# SupplyBox_v4.net
KiCad netlist of a schematic drawn in Altium Designer
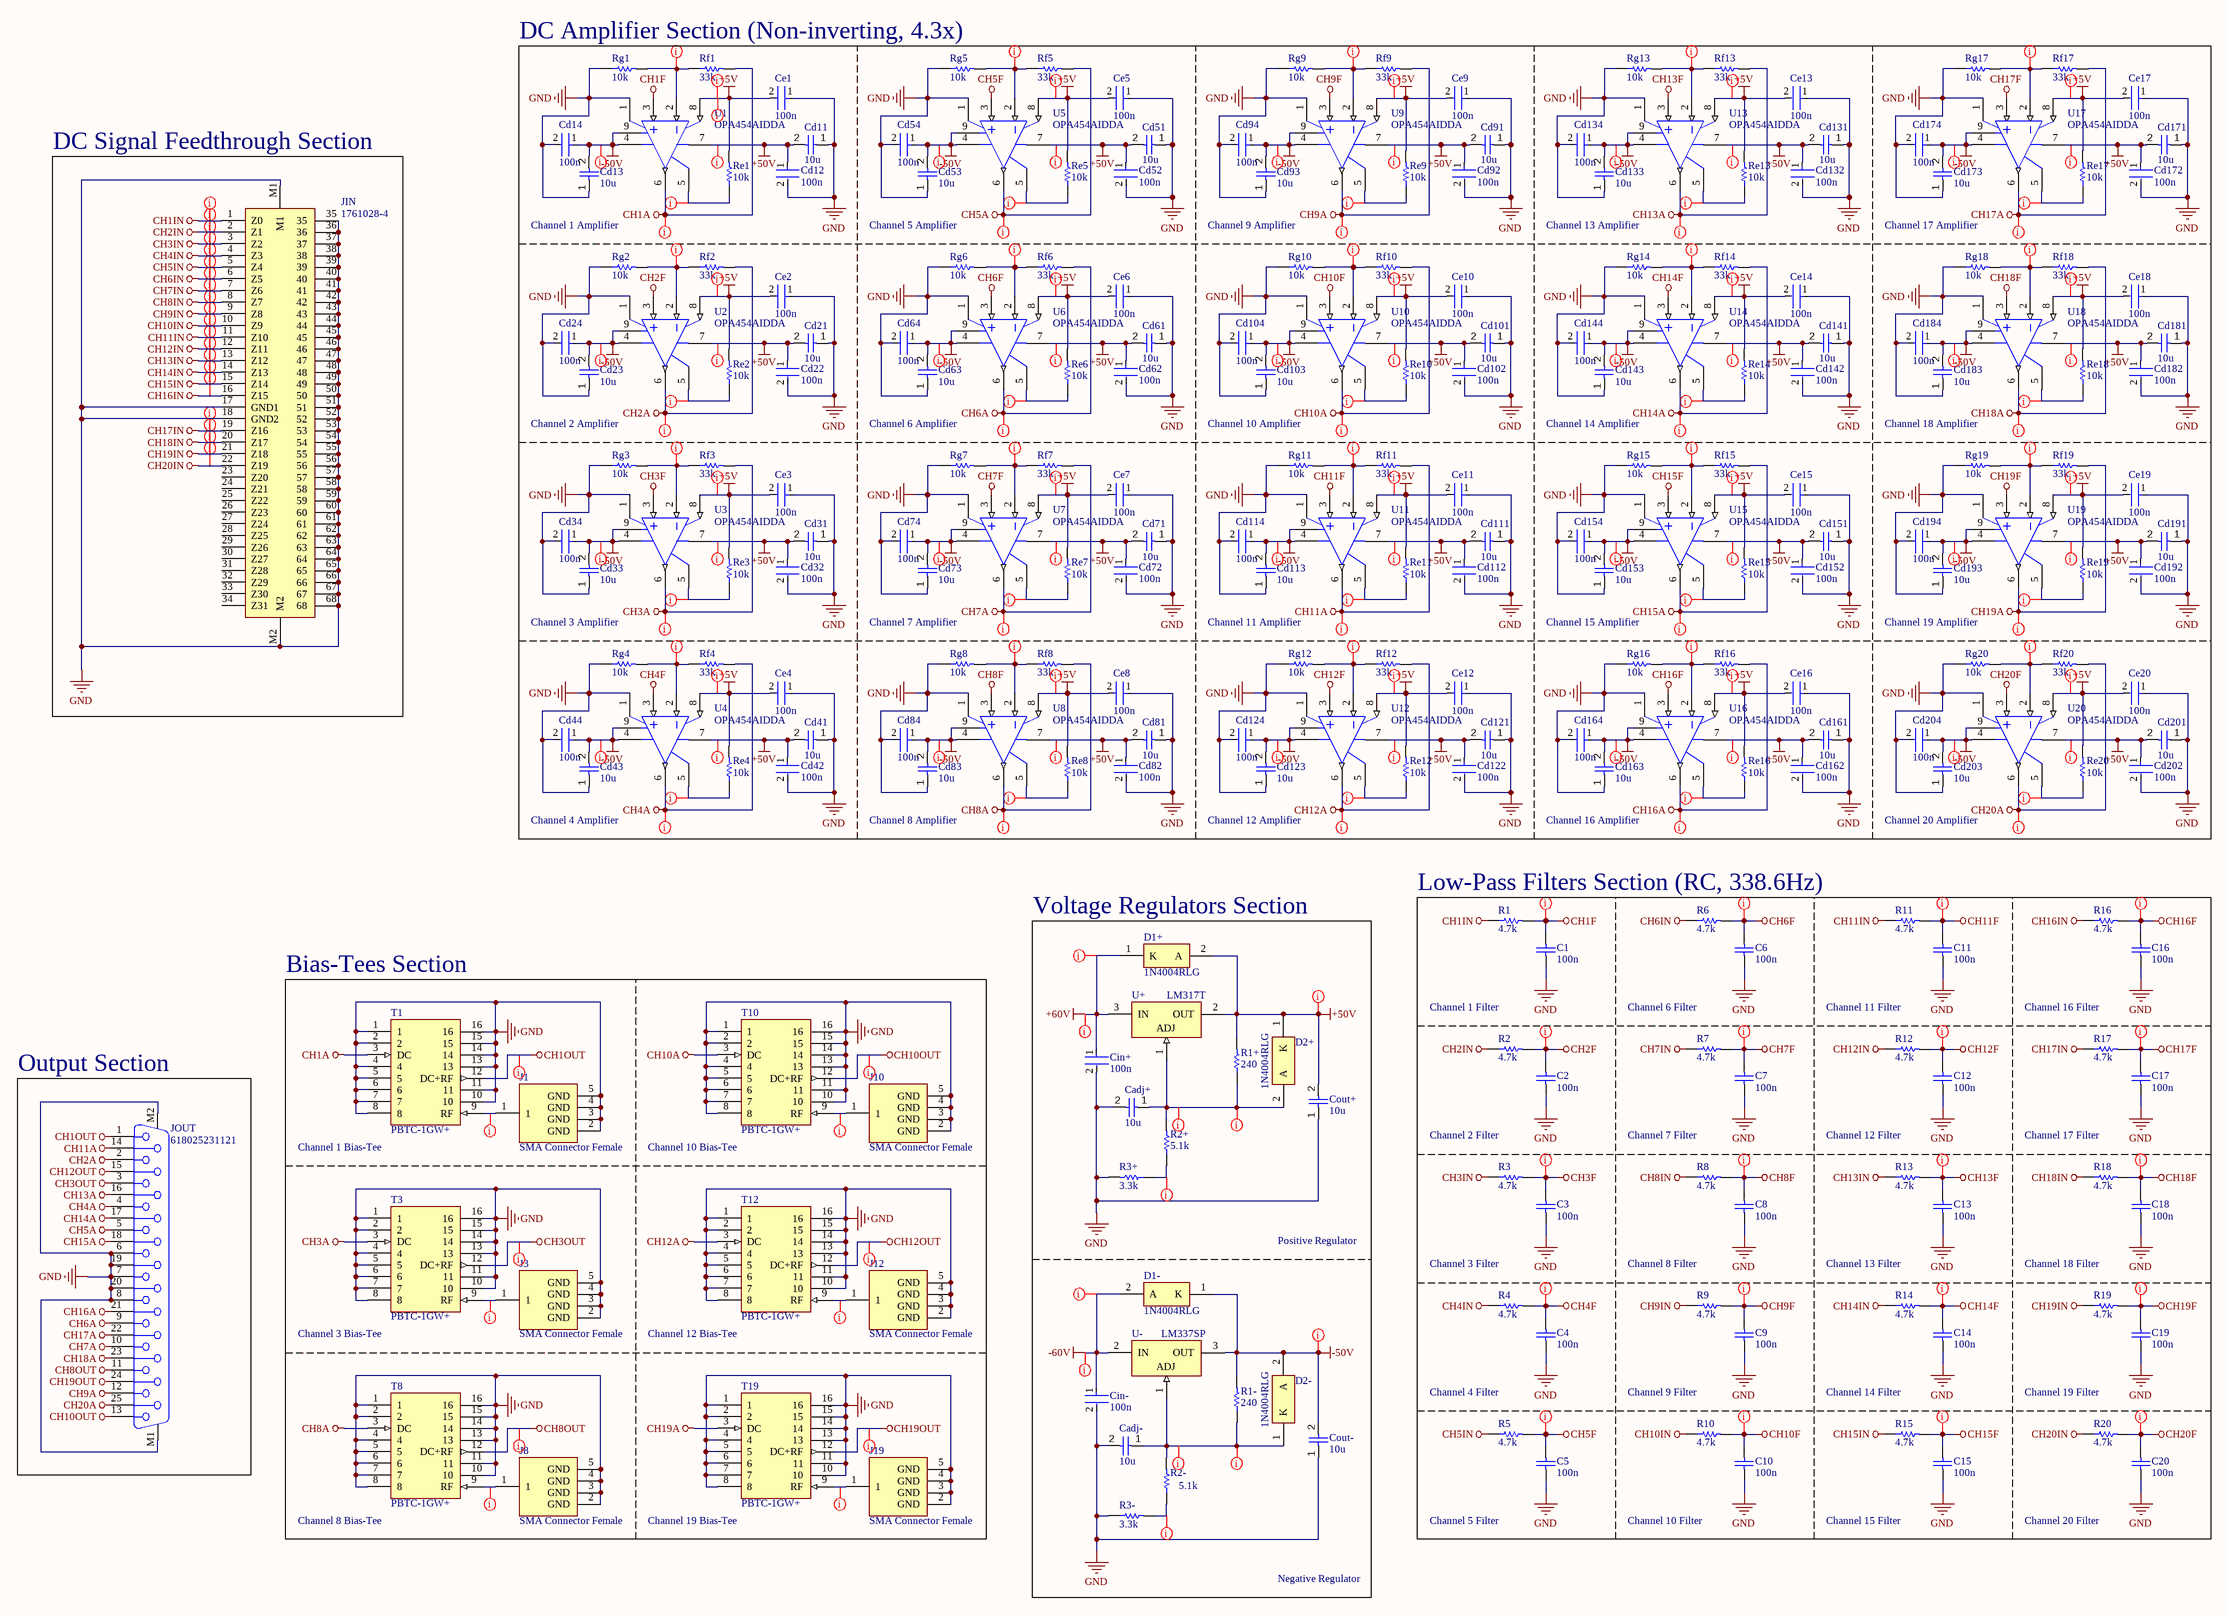
[diagram p0: SupplyBox_v4.SchDoc]

(export (version "E")
  (design (tool "Eeschema 10.0.6"))
  (components
    (comp (ref "C1")
      (value "100n")
      (footprint "CAPC2013X145X48NL20T23")
      (fields (field (name "MANUFACTURER") "Vitramon") (field (name "PART NUMBER") "VJ0805Y104KNAAT"))
      (libsource (lib "Altium Content Vault") (part "CAP"))
    )
    (comp (ref "C2")
      (value "100n")
      (footprint "CAPC2013X145X48NL20T23")
      (fields (field (name "MANUFACTURER") "Vitramon") (field (name "PART NUMBER") "VJ0805Y104KNAAT"))
      (libsource (lib "Altium Content Vault") (part "CAP"))
    )
    (comp (ref "C3")
      (value "100n")
      (footprint "CAPC2013X145X48NL20T23")
      (fields (field (name "MANUFACTURER") "Vitramon") (field (name "PART NUMBER") "VJ0805Y104KNAAT"))
      (libsource (lib "Altium Content Vault") (part "CAP"))
    )
    (comp (ref "C4")
      (value "100n")
      (footprint "CAPC2013X145X48NL20T23")
      (fields (field (name "MANUFACTURER") "Vitramon") (field (name "PART NUMBER") "VJ0805Y104KNAAT"))
      (libsource (lib "Altium Content Vault") (part "CAP"))
    )
    (comp (ref "C5")
      (value "100n")
      (footprint "CAPC2013X145X48NL20T23")
      (fields (field (name "MANUFACTURER") "Vitramon") (field (name "PART NUMBER") "VJ0805Y104KNAAT"))
      (libsource (lib "Altium Content Vault") (part "CAP"))
    )
    (comp (ref "C6")
      (value "100n")
      (footprint "CAPC2013X145X48NL20T23")
      (fields (field (name "MANUFACTURER") "Vitramon") (field (name "PART NUMBER") "VJ0805Y104KNAAT"))
      (libsource (lib "Altium Content Vault") (part "CAP"))
    )
    (comp (ref "C7")
      (value "100n")
      (footprint "CAPC2013X145X48NL20T23")
      (fields (field (name "MANUFACTURER") "Vitramon") (field (name "PART NUMBER") "VJ0805Y104KNAAT"))
      (libsource (lib "Altium Content Vault") (part "CAP"))
    )
    (comp (ref "C8")
      (value "100n")
      (footprint "CAPC2013X145X48NL20T23")
      (fields (field (name "MANUFACTURER") "Vitramon") (field (name "PART NUMBER") "VJ0805Y104KNAAT"))
      (libsource (lib "Altium Content Vault") (part "CAP"))
    )
    (comp (ref "C9")
      (value "100n")
      (footprint "CAPC2013X145X48NL20T23")
      (fields (field (name "MANUFACTURER") "Vitramon") (field (name "PART NUMBER") "VJ0805Y104KNAAT"))
      (libsource (lib "Altium Content Vault") (part "CAP"))
    )
    (comp (ref "C10")
      (value "100n")
      (footprint "CAPC2013X145X48NL20T23")
      (fields (field (name "MANUFACTURER") "Vitramon") (field (name "PART NUMBER") "VJ0805Y104KNAAT"))
      (libsource (lib "Altium Content Vault") (part "CAP"))
    )
    (comp (ref "C11")
      (value "100n")
      (footprint "CAPC2013X145X48NL20T23")
      (fields (field (name "MANUFACTURER") "Vitramon") (field (name "PART NUMBER") "VJ0805Y104KNAAT"))
      (libsource (lib "Altium Content Vault") (part "CAP"))
    )
    (comp (ref "C12")
      (value "100n")
      (footprint "CAPC2013X145X48NL20T23")
      (fields (field (name "MANUFACTURER") "Vitramon") (field (name "PART NUMBER") "VJ0805Y104KNAAT"))
      (libsource (lib "Altium Content Vault") (part "CAP"))
    )
    (comp (ref "C13")
      (value "100n")
      (footprint "CAPC2013X145X48NL20T23")
      (fields (field (name "MANUFACTURER") "Vitramon") (field (name "PART NUMBER") "VJ0805Y104KNAAT"))
      (libsource (lib "Altium Content Vault") (part "CAP"))
    )
    (comp (ref "C14")
      (value "100n")
      (footprint "CAPC2013X145X48NL20T23")
      (fields (field (name "MANUFACTURER") "Vitramon") (field (name "PART NUMBER") "VJ0805Y104KNAAT"))
      (libsource (lib "Altium Content Vault") (part "CAP"))
    )
    (comp (ref "C15")
      (value "100n")
      (footprint "CAPC2013X145X48NL20T23")
      (fields (field (name "MANUFACTURER") "Vitramon") (field (name "PART NUMBER") "VJ0805Y104KNAAT"))
      (libsource (lib "Altium Content Vault") (part "CAP"))
    )
    (comp (ref "C16")
      (value "100n")
      (footprint "CAPC2013X145X48NL20T23")
      (fields (field (name "MANUFACTURER") "Vitramon") (field (name "PART NUMBER") "VJ0805Y104KNAAT"))
      (libsource (lib "Altium Content Vault") (part "CAP"))
    )
    (comp (ref "C17")
      (value "100n")
      (footprint "CAPC2013X145X48NL20T23")
      (fields (field (name "MANUFACTURER") "Vitramon") (field (name "PART NUMBER") "VJ0805Y104KNAAT"))
      (libsource (lib "Altium Content Vault") (part "CAP"))
    )
    (comp (ref "C18")
      (value "100n")
      (footprint "CAPC2013X145X48NL20T23")
      (fields (field (name "MANUFACTURER") "Vitramon") (field (name "PART NUMBER") "VJ0805Y104KNAAT"))
      (libsource (lib "Altium Content Vault") (part "CAP"))
    )
    (comp (ref "C19")
      (value "100n")
      (footprint "CAPC2013X145X48NL20T23")
      (fields (field (name "MANUFACTURER") "Vitramon") (field (name "PART NUMBER") "VJ0805Y104KNAAT"))
      (libsource (lib "Altium Content Vault") (part "CAP"))
    )
    (comp (ref "C20")
      (value "100n")
      (footprint "CAPC2013X145X48NL20T23")
      (fields (field (name "MANUFACTURER") "Vitramon") (field (name "PART NUMBER") "VJ0805Y104KNAAT"))
      (libsource (lib "Altium Content Vault") (part "CAP"))
    )
    (comp (ref "Cadj+")
      (value "10u")
      (footprint "RAHV1100M1UCC8002E-Footprint-1")
      (libsource (lib "Li-Ren Liu") (part "CAP-NP-2"))
    )
    (comp (ref "Cadj-")
      (value "10u")
      (footprint "RAHV1100M1UCC8002E-Footprint-1")
      (libsource (lib "Li-Ren Liu") (part "CAP-NP-2"))
    )
    (comp (ref "Cd11")
      (value "10u")
      (footprint "RAHV1100M1UCC8002E-Footprint-1")
      (libsource (lib "Li-Ren Liu") (part "CAP-NP-2"))
    )
    (comp (ref "Cd12")
      (value "100n")
      (footprint "FP-CC0805-0_85-MFG")
      (description "CAP CER 0.1UF 25V X7R 0805")
      (fields (field (name "MANUFACTURER PART NUMBER") "CC0805KRX7R8BB104") (field (name "TOLERANCE") "0.1"))
      (libsource (lib "Altium Content Vault") (part "11868f565c42a9108669ba33697ecf6"))
    )
    (comp (ref "Cd13")
      (value "10u")
      (footprint "RAHV1100M1UCC8002E-Footprint-1")
      (libsource (lib "Li-Ren Liu") (part "CAP-NP-2"))
    )
    (comp (ref "Cd14")
      (value "100n")
      (footprint "FP-CC0805-0_85-MFG")
      (description "CAP CER 0.1UF 25V X7R 0805")
      (fields (field (name "MANUFACTURER PART NUMBER") "CC0805KRX7R8BB104") (field (name "TOLERANCE") "0.1"))
      (libsource (lib "Altium Content Vault") (part "11868f565c42a9108669ba33697ecf6"))
    )
    (comp (ref "Cd21")
      (value "10u")
      (footprint "RAHV1100M1UCC8002E-Footprint-1")
      (libsource (lib "Li-Ren Liu") (part "CAP-NP-2"))
    )
    (comp (ref "Cd22")
      (value "100n")
      (footprint "FP-CC0805-0_85-MFG")
      (description "CAP CER 0.1UF 25V X7R 0805")
      (fields (field (name "MANUFACTURER PART NUMBER") "CC0805KRX7R8BB104") (field (name "TOLERANCE") "0.1"))
      (libsource (lib "Altium Content Vault") (part "11868f565c42a9108669ba33697ecf6"))
    )
    (comp (ref "Cd23")
      (value "10u")
      (footprint "RAHV1100M1UCC8002E-Footprint-1")
      (libsource (lib "Li-Ren Liu") (part "CAP-NP-2"))
    )
    (comp (ref "Cd24")
      (value "100n")
      (footprint "FP-CC0805-0_85-MFG")
      (description "CAP CER 0.1UF 25V X7R 0805")
      (fields (field (name "MANUFACTURER PART NUMBER") "CC0805KRX7R8BB104") (field (name "TOLERANCE") "0.1"))
      (libsource (lib "Altium Content Vault") (part "11868f565c42a9108669ba33697ecf6"))
    )
    (comp (ref "Cd31")
      (value "10u")
      (footprint "RAHV1100M1UCC8002E-Footprint-1")
      (libsource (lib "Li-Ren Liu") (part "CAP-NP-2"))
    )
    (comp (ref "Cd32")
      (value "100n")
      (footprint "FP-CC0805-0_85-MFG")
      (description "CAP CER 0.1UF 25V X7R 0805")
      (fields (field (name "MANUFACTURER PART NUMBER") "CC0805KRX7R8BB104") (field (name "TOLERANCE") "0.1"))
      (libsource (lib "Altium Content Vault") (part "11868f565c42a9108669ba33697ecf6"))
    )
    (comp (ref "Cd33")
      (value "10u")
      (footprint "RAHV1100M1UCC8002E-Footprint-1")
      (libsource (lib "Li-Ren Liu") (part "CAP-NP-2"))
    )
    (comp (ref "Cd34")
      (value "100n")
      (footprint "FP-CC0805-0_85-MFG")
      (description "CAP CER 0.1UF 25V X7R 0805")
      (fields (field (name "MANUFACTURER PART NUMBER") "CC0805KRX7R8BB104") (field (name "TOLERANCE") "0.1"))
      (libsource (lib "Altium Content Vault") (part "11868f565c42a9108669ba33697ecf6"))
    )
    (comp (ref "Cd41")
      (value "10u")
      (footprint "RAHV1100M1UCC8002E-Footprint-1")
      (libsource (lib "Li-Ren Liu") (part "CAP-NP-2"))
    )
    (comp (ref "Cd42")
      (value "100n")
      (footprint "FP-CC0805-0_85-MFG")
      (description "CAP CER 0.1UF 25V X7R 0805")
      (fields (field (name "MANUFACTURER PART NUMBER") "CC0805KRX7R8BB104") (field (name "TOLERANCE") "0.1"))
      (libsource (lib "Altium Content Vault") (part "11868f565c42a9108669ba33697ecf6"))
    )
    (comp (ref "Cd43")
      (value "10u")
      (footprint "RAHV1100M1UCC8002E-Footprint-1")
      (libsource (lib "Li-Ren Liu") (part "CAP-NP-2"))
    )
    (comp (ref "Cd44")
      (value "100n")
      (footprint "FP-CC0805-0_85-MFG")
      (description "CAP CER 0.1UF 25V X7R 0805")
      (fields (field (name "MANUFACTURER PART NUMBER") "CC0805KRX7R8BB104") (field (name "TOLERANCE") "0.1"))
      (libsource (lib "Altium Content Vault") (part "11868f565c42a9108669ba33697ecf6"))
    )
    (comp (ref "Cd51")
      (value "10u")
      (footprint "RAHV1100M1UCC8002E-Footprint-1")
      (libsource (lib "Li-Ren Liu") (part "CAP-NP-2"))
    )
    (comp (ref "Cd52")
      (value "100n")
      (footprint "FP-CC0805-0_85-MFG")
      (description "CAP CER 0.1UF 25V X7R 0805")
      (fields (field (name "MANUFACTURER PART NUMBER") "CC0805KRX7R8BB104") (field (name "TOLERANCE") "0.1"))
      (libsource (lib "Altium Content Vault") (part "11868f565c42a9108669ba33697ecf6"))
    )
    (comp (ref "Cd53")
      (value "10u")
      (footprint "RAHV1100M1UCC8002E-Footprint-1")
      (libsource (lib "Li-Ren Liu") (part "CAP-NP-2"))
    )
    (comp (ref "Cd54")
      (value "100n")
      (footprint "FP-CC0805-0_85-MFG")
      (description "CAP CER 0.1UF 25V X7R 0805")
      (fields (field (name "MANUFACTURER PART NUMBER") "CC0805KRX7R8BB104") (field (name "TOLERANCE") "0.1"))
      (libsource (lib "Altium Content Vault") (part "11868f565c42a9108669ba33697ecf6"))
    )
    (comp (ref "Cd61")
      (value "10u")
      (footprint "RAHV1100M1UCC8002E-Footprint-1")
      (libsource (lib "Li-Ren Liu") (part "CAP-NP-2"))
    )
    (comp (ref "Cd62")
      (value "100n")
      (footprint "FP-CC0805-0_85-MFG")
      (description "CAP CER 0.1UF 25V X7R 0805")
      (fields (field (name "MANUFACTURER PART NUMBER") "CC0805KRX7R8BB104") (field (name "TOLERANCE") "0.1"))
      (libsource (lib "Altium Content Vault") (part "11868f565c42a9108669ba33697ecf6"))
    )
    (comp (ref "Cd63")
      (value "10u")
      (footprint "RAHV1100M1UCC8002E-Footprint-1")
      (libsource (lib "Li-Ren Liu") (part "CAP-NP-2"))
    )
    (comp (ref "Cd64")
      (value "100n")
      (footprint "FP-CC0805-0_85-MFG")
      (description "CAP CER 0.1UF 25V X7R 0805")
      (fields (field (name "MANUFACTURER PART NUMBER") "CC0805KRX7R8BB104") (field (name "TOLERANCE") "0.1"))
      (libsource (lib "Altium Content Vault") (part "11868f565c42a9108669ba33697ecf6"))
    )
    (comp (ref "Cd71")
      (value "10u")
      (footprint "RAHV1100M1UCC8002E-Footprint-1")
      (libsource (lib "Li-Ren Liu") (part "CAP-NP-2"))
    )
    (comp (ref "Cd72")
      (value "100n")
      (footprint "FP-CC0805-0_85-MFG")
      (description "CAP CER 0.1UF 25V X7R 0805")
      (fields (field (name "MANUFACTURER PART NUMBER") "CC0805KRX7R8BB104") (field (name "TOLERANCE") "0.1"))
      (libsource (lib "Altium Content Vault") (part "11868f565c42a9108669ba33697ecf6"))
    )
    (comp (ref "Cd73")
      (value "10u")
      (footprint "RAHV1100M1UCC8002E-Footprint-1")
      (libsource (lib "Li-Ren Liu") (part "CAP-NP-2"))
    )
    (comp (ref "Cd74")
      (value "100n")
      (footprint "FP-CC0805-0_85-MFG")
      (description "CAP CER 0.1UF 25V X7R 0805")
      (fields (field (name "MANUFACTURER PART NUMBER") "CC0805KRX7R8BB104") (field (name "TOLERANCE") "0.1"))
      (libsource (lib "Altium Content Vault") (part "11868f565c42a9108669ba33697ecf6"))
    )
    (comp (ref "Cd81")
      (value "10u")
      (footprint "RAHV1100M1UCC8002E-Footprint-1")
      (libsource (lib "Li-Ren Liu") (part "CAP-NP-2"))
    )
    (comp (ref "Cd82")
      (value "100n")
      (footprint "FP-CC0805-0_85-MFG")
      (description "CAP CER 0.1UF 25V X7R 0805")
      (fields (field (name "MANUFACTURER PART NUMBER") "CC0805KRX7R8BB104") (field (name "TOLERANCE") "0.1"))
      (libsource (lib "Altium Content Vault") (part "11868f565c42a9108669ba33697ecf6"))
    )
    (comp (ref "Cd83")
      (value "10u")
      (footprint "RAHV1100M1UCC8002E-Footprint-1")
      (libsource (lib "Li-Ren Liu") (part "CAP-NP-2"))
    )
    (comp (ref "Cd84")
      (value "100n")
      (footprint "FP-CC0805-0_85-MFG")
      (description "CAP CER 0.1UF 25V X7R 0805")
      (fields (field (name "MANUFACTURER PART NUMBER") "CC0805KRX7R8BB104") (field (name "TOLERANCE") "0.1"))
      (libsource (lib "Altium Content Vault") (part "11868f565c42a9108669ba33697ecf6"))
    )
    (comp (ref "Cd91")
      (value "10u")
      (footprint "RAHV1100M1UCC8002E-Footprint-1")
      (libsource (lib "Li-Ren Liu") (part "CAP-NP-2"))
    )
    (comp (ref "Cd92")
      (value "100n")
      (footprint "FP-CC0805-0_85-MFG")
      (description "CAP CER 0.1UF 25V X7R 0805")
      (fields (field (name "MANUFACTURER PART NUMBER") "CC0805KRX7R8BB104") (field (name "TOLERANCE") "0.1"))
      (libsource (lib "Altium Content Vault") (part "11868f565c42a9108669ba33697ecf6"))
    )
    (comp (ref "Cd93")
      (value "10u")
      (footprint "RAHV1100M1UCC8002E-Footprint-1")
      (libsource (lib "Li-Ren Liu") (part "CAP-NP-2"))
    )
    (comp (ref "Cd94")
      (value "100n")
      (footprint "FP-CC0805-0_85-MFG")
      (description "CAP CER 0.1UF 25V X7R 0805")
      (fields (field (name "MANUFACTURER PART NUMBER") "CC0805KRX7R8BB104") (field (name "TOLERANCE") "0.1"))
      (libsource (lib "Altium Content Vault") (part "11868f565c42a9108669ba33697ecf6"))
    )
    (comp (ref "Cd101")
      (value "10u")
      (footprint "RAHV1100M1UCC8002E-Footprint-1")
      (libsource (lib "Li-Ren Liu") (part "CAP-NP-2"))
    )
    (comp (ref "Cd102")
      (value "100n")
      (footprint "FP-CC0805-0_85-MFG")
      (description "CAP CER 0.1UF 25V X7R 0805")
      (fields (field (name "MANUFACTURER PART NUMBER") "CC0805KRX7R8BB104") (field (name "TOLERANCE") "0.1"))
      (libsource (lib "Altium Content Vault") (part "11868f565c42a9108669ba33697ecf6"))
    )
    (comp (ref "Cd103")
      (value "10u")
      (footprint "RAHV1100M1UCC8002E-Footprint-1")
      (libsource (lib "Li-Ren Liu") (part "CAP-NP-2"))
    )
    (comp (ref "Cd104")
      (value "100n")
      (footprint "FP-CC0805-0_85-MFG")
      (description "CAP CER 0.1UF 25V X7R 0805")
      (fields (field (name "MANUFACTURER PART NUMBER") "CC0805KRX7R8BB104") (field (name "TOLERANCE") "0.1"))
      (libsource (lib "Altium Content Vault") (part "11868f565c42a9108669ba33697ecf6"))
    )
    (comp (ref "Cd111")
      (value "10u")
      (footprint "RAHV1100M1UCC8002E-Footprint-1")
      (libsource (lib "Li-Ren Liu") (part "CAP-NP-2"))
    )
    (comp (ref "Cd112")
      (value "100n")
      (footprint "FP-CC0805-0_85-MFG")
      (description "CAP CER 0.1UF 25V X7R 0805")
      (fields (field (name "MANUFACTURER PART NUMBER") "CC0805KRX7R8BB104") (field (name "TOLERANCE") "0.1"))
      (libsource (lib "Altium Content Vault") (part "11868f565c42a9108669ba33697ecf6"))
    )
    (comp (ref "Cd113")
      (value "10u")
      (footprint "RAHV1100M1UCC8002E-Footprint-1")
      (libsource (lib "Li-Ren Liu") (part "CAP-NP-2"))
    )
    (comp (ref "Cd114")
      (value "100n")
      (footprint "FP-CC0805-0_85-MFG")
      (description "CAP CER 0.1UF 25V X7R 0805")
      (fields (field (name "MANUFACTURER PART NUMBER") "CC0805KRX7R8BB104") (field (name "TOLERANCE") "0.1"))
      (libsource (lib "Altium Content Vault") (part "11868f565c42a9108669ba33697ecf6"))
    )
    (comp (ref "Cd121")
      (value "10u")
      (footprint "RAHV1100M1UCC8002E-Footprint-1")
      (libsource (lib "Li-Ren Liu") (part "CAP-NP-2"))
    )
    (comp (ref "Cd122")
      (value "100n")
      (footprint "FP-CC0805-0_85-MFG")
      (description "CAP CER 0.1UF 25V X7R 0805")
      (fields (field (name "MANUFACTURER PART NUMBER") "CC0805KRX7R8BB104") (field (name "TOLERANCE") "0.1"))
      (libsource (lib "Altium Content Vault") (part "11868f565c42a9108669ba33697ecf6"))
    )
    (comp (ref "Cd123")
      (value "10u")
      (footprint "RAHV1100M1UCC8002E-Footprint-1")
      (libsource (lib "Li-Ren Liu") (part "CAP-NP-2"))
    )
    (comp (ref "Cd124")
      (value "100n")
      (footprint "FP-CC0805-0_85-MFG")
      (description "CAP CER 0.1UF 25V X7R 0805")
      (fields (field (name "MANUFACTURER PART NUMBER") "CC0805KRX7R8BB104") (field (name "TOLERANCE") "0.1"))
      (libsource (lib "Altium Content Vault") (part "11868f565c42a9108669ba33697ecf6"))
    )
    (comp (ref "Cd131")
      (value "10u")
      (footprint "RAHV1100M1UCC8002E-Footprint-1")
      (libsource (lib "Li-Ren Liu") (part "CAP-NP-2"))
    )
    (comp (ref "Cd132")
      (value "100n")
      (footprint "FP-CC0805-0_85-MFG")
      (description "CAP CER 0.1UF 25V X7R 0805")
      (fields (field (name "MANUFACTURER PART NUMBER") "CC0805KRX7R8BB104") (field (name "TOLERANCE") "0.1"))
      (libsource (lib "Altium Content Vault") (part "11868f565c42a9108669ba33697ecf6"))
    )
    (comp (ref "Cd133")
      (value "10u")
      (footprint "RAHV1100M1UCC8002E-Footprint-1")
      (libsource (lib "Li-Ren Liu") (part "CAP-NP-2"))
    )
    (comp (ref "Cd134")
      (value "100n")
      (footprint "FP-CC0805-0_85-MFG")
      (description "CAP CER 0.1UF 25V X7R 0805")
      (fields (field (name "MANUFACTURER PART NUMBER") "CC0805KRX7R8BB104") (field (name "TOLERANCE") "0.1"))
      (libsource (lib "Altium Content Vault") (part "11868f565c42a9108669ba33697ecf6"))
    )
    (comp (ref "Cd141")
      (value "10u")
      (footprint "RAHV1100M1UCC8002E-Footprint-1")
      (libsource (lib "Li-Ren Liu") (part "CAP-NP-2"))
    )
    (comp (ref "Cd142")
      (value "100n")
      (footprint "FP-CC0805-0_85-MFG")
      (description "CAP CER 0.1UF 25V X7R 0805")
      (fields (field (name "MANUFACTURER PART NUMBER") "CC0805KRX7R8BB104") (field (name "TOLERANCE") "0.1"))
      (libsource (lib "Altium Content Vault") (part "11868f565c42a9108669ba33697ecf6"))
    )
    (comp (ref "Cd143")
      (value "10u")
      (footprint "RAHV1100M1UCC8002E-Footprint-1")
      (libsource (lib "Li-Ren Liu") (part "CAP-NP-2"))
    )
    (comp (ref "Cd144")
      (value "100n")
      (footprint "FP-CC0805-0_85-MFG")
      (description "CAP CER 0.1UF 25V X7R 0805")
      (fields (field (name "MANUFACTURER PART NUMBER") "CC0805KRX7R8BB104") (field (name "TOLERANCE") "0.1"))
      (libsource (lib "Altium Content Vault") (part "11868f565c42a9108669ba33697ecf6"))
    )
    (comp (ref "Cd151")
      (value "10u")
      (footprint "RAHV1100M1UCC8002E-Footprint-1")
      (libsource (lib "Li-Ren Liu") (part "CAP-NP-2"))
    )
    (comp (ref "Cd152")
      (value "100n")
      (footprint "FP-CC0805-0_85-MFG")
      (description "CAP CER 0.1UF 25V X7R 0805")
      (fields (field (name "MANUFACTURER PART NUMBER") "CC0805KRX7R8BB104") (field (name "TOLERANCE") "0.1"))
      (libsource (lib "Altium Content Vault") (part "11868f565c42a9108669ba33697ecf6"))
    )
    (comp (ref "Cd153")
      (value "10u")
      (footprint "RAHV1100M1UCC8002E-Footprint-1")
      (libsource (lib "Li-Ren Liu") (part "CAP-NP-2"))
    )
    (comp (ref "Cd154")
      (value "100n")
      (footprint "FP-CC0805-0_85-MFG")
      (description "CAP CER 0.1UF 25V X7R 0805")
      (fields (field (name "MANUFACTURER PART NUMBER") "CC0805KRX7R8BB104") (field (name "TOLERANCE") "0.1"))
      (libsource (lib "Altium Content Vault") (part "11868f565c42a9108669ba33697ecf6"))
    )
    (comp (ref "Cd161")
      (value "10u")
      (footprint "RAHV1100M1UCC8002E-Footprint-1")
      (libsource (lib "Li-Ren Liu") (part "CAP-NP-2"))
    )
    (comp (ref "Cd162")
      (value "100n")
      (footprint "FP-CC0805-0_85-MFG")
      (description "CAP CER 0.1UF 25V X7R 0805")
      (fields (field (name "MANUFACTURER PART NUMBER") "CC0805KRX7R8BB104") (field (name "TOLERANCE") "0.1"))
      (libsource (lib "Altium Content Vault") (part "11868f565c42a9108669ba33697ecf6"))
    )
    (comp (ref "Cd163")
      (value "10u")
      (footprint "RAHV1100M1UCC8002E-Footprint-1")
      (libsource (lib "Li-Ren Liu") (part "CAP-NP-2"))
    )
    (comp (ref "Cd164")
      (value "100n")
      (footprint "FP-CC0805-0_85-MFG")
      (description "CAP CER 0.1UF 25V X7R 0805")
      (fields (field (name "MANUFACTURER PART NUMBER") "CC0805KRX7R8BB104") (field (name "TOLERANCE") "0.1"))
      (libsource (lib "Altium Content Vault") (part "11868f565c42a9108669ba33697ecf6"))
    )
    (comp (ref "Cd171")
      (value "10u")
      (footprint "RAHV1100M1UCC8002E-Footprint-1")
      (libsource (lib "Li-Ren Liu") (part "CAP-NP-2"))
    )
    (comp (ref "Cd172")
      (value "100n")
      (footprint "FP-CC0805-0_85-MFG")
      (description "CAP CER 0.1UF 25V X7R 0805")
      (fields (field (name "MANUFACTURER PART NUMBER") "CC0805KRX7R8BB104") (field (name "TOLERANCE") "0.1"))
      (libsource (lib "Altium Content Vault") (part "11868f565c42a9108669ba33697ecf6"))
    )
    (comp (ref "Cd173")
      (value "10u")
      (footprint "RAHV1100M1UCC8002E-Footprint-1")
      (libsource (lib "Li-Ren Liu") (part "CAP-NP-2"))
    )
    (comp (ref "Cd174")
      (value "100n")
      (footprint "FP-CC0805-0_85-MFG")
      (description "CAP CER 0.1UF 25V X7R 0805")
      (fields (field (name "MANUFACTURER PART NUMBER") "CC0805KRX7R8BB104") (field (name "TOLERANCE") "0.1"))
      (libsource (lib "Altium Content Vault") (part "11868f565c42a9108669ba33697ecf6"))
    )
    (comp (ref "Cd181")
      (value "10u")
      (footprint "RAHV1100M1UCC8002E-Footprint-1")
      (libsource (lib "Li-Ren Liu") (part "CAP-NP-2"))
    )
    (comp (ref "Cd182")
      (value "100n")
      (footprint "FP-CC0805-0_85-MFG")
      (description "CAP CER 0.1UF 25V X7R 0805")
      (fields (field (name "MANUFACTURER PART NUMBER") "CC0805KRX7R8BB104") (field (name "TOLERANCE") "0.1"))
      (libsource (lib "Altium Content Vault") (part "11868f565c42a9108669ba33697ecf6"))
    )
    (comp (ref "Cd183")
      (value "10u")
      (footprint "RAHV1100M1UCC8002E-Footprint-1")
      (libsource (lib "Li-Ren Liu") (part "CAP-NP-2"))
    )
    (comp (ref "Cd184")
      (value "100n")
      (footprint "FP-CC0805-0_85-MFG")
      (description "CAP CER 0.1UF 25V X7R 0805")
      (fields (field (name "MANUFACTURER PART NUMBER") "CC0805KRX7R8BB104") (field (name "TOLERANCE") "0.1"))
      (libsource (lib "Altium Content Vault") (part "11868f565c42a9108669ba33697ecf6"))
    )
    (comp (ref "Cd191")
      (value "10u")
      (footprint "RAHV1100M1UCC8002E-Footprint-1")
      (libsource (lib "Li-Ren Liu") (part "CAP-NP-2"))
    )
    (comp (ref "Cd192")
      (value "100n")
      (footprint "FP-CC0805-0_85-MFG")
      (description "CAP CER 0.1UF 25V X7R 0805")
      (fields (field (name "MANUFACTURER PART NUMBER") "CC0805KRX7R8BB104") (field (name "TOLERANCE") "0.1"))
      (libsource (lib "Altium Content Vault") (part "11868f565c42a9108669ba33697ecf6"))
    )
    (comp (ref "Cd193")
      (value "10u")
      (footprint "RAHV1100M1UCC8002E-Footprint-1")
      (libsource (lib "Li-Ren Liu") (part "CAP-NP-2"))
    )
    (comp (ref "Cd194")
      (value "100n")
      (footprint "FP-CC0805-0_85-MFG")
      (description "CAP CER 0.1UF 25V X7R 0805")
      (fields (field (name "MANUFACTURER PART NUMBER") "CC0805KRX7R8BB104") (field (name "TOLERANCE") "0.1"))
      (libsource (lib "Altium Content Vault") (part "11868f565c42a9108669ba33697ecf6"))
    )
    (comp (ref "Cd201")
      (value "10u")
      (footprint "RAHV1100M1UCC8002E-Footprint-1")
      (libsource (lib "Li-Ren Liu") (part "CAP-NP-2"))
    )
    (comp (ref "Cd202")
      (value "100n")
      (footprint "FP-CC0805-0_85-MFG")
      (description "CAP CER 0.1UF 25V X7R 0805")
      (fields (field (name "MANUFACTURER PART NUMBER") "CC0805KRX7R8BB104") (field (name "TOLERANCE") "0.1"))
      (libsource (lib "Altium Content Vault") (part "11868f565c42a9108669ba33697ecf6"))
    )
    (comp (ref "Cd203")
      (value "10u")
      (footprint "RAHV1100M1UCC8002E-Footprint-1")
      (libsource (lib "Li-Ren Liu") (part "CAP-NP-2"))
    )
    (comp (ref "Cd204")
      (value "100n")
      (footprint "FP-CC0805-0_85-MFG")
      (description "CAP CER 0.1UF 25V X7R 0805")
      (fields (field (name "MANUFACTURER PART NUMBER") "CC0805KRX7R8BB104") (field (name "TOLERANCE") "0.1"))
      (libsource (lib "Altium Content Vault") (part "11868f565c42a9108669ba33697ecf6"))
    )
    (comp (ref "Ce1")
      (value "100n")
      (footprint "FP-CC0805-0_85-MFG")
      (description "CAP CER 0.1UF 25V X7R 0805")
      (fields (field (name "MANUFACTURER PART NUMBER") "CC0805KRX7R8BB104") (field (name "TOLERANCE") "0.1"))
      (libsource (lib "Altium Content Vault") (part "11868f565c42a9108669ba33697ecf6"))
    )
    (comp (ref "Ce2")
      (value "100n")
      (footprint "FP-CC0805-0_85-MFG")
      (description "CAP CER 0.1UF 25V X7R 0805")
      (fields (field (name "MANUFACTURER PART NUMBER") "CC0805KRX7R8BB104") (field (name "TOLERANCE") "0.1"))
      (libsource (lib "Altium Content Vault") (part "11868f565c42a9108669ba33697ecf6"))
    )
    (comp (ref "Ce3")
      (value "100n")
      (footprint "FP-CC0805-0_85-MFG")
      (description "CAP CER 0.1UF 25V X7R 0805")
      (fields (field (name "MANUFACTURER PART NUMBER") "CC0805KRX7R8BB104") (field (name "TOLERANCE") "0.1"))
      (libsource (lib "Altium Content Vault") (part "11868f565c42a9108669ba33697ecf6"))
    )
    (comp (ref "Ce4")
      (value "100n")
      (footprint "FP-CC0805-0_85-MFG")
      (description "CAP CER 0.1UF 25V X7R 0805")
      (fields (field (name "MANUFACTURER PART NUMBER") "CC0805KRX7R8BB104") (field (name "TOLERANCE") "0.1"))
      (libsource (lib "Altium Content Vault") (part "11868f565c42a9108669ba33697ecf6"))
    )
    (comp (ref "Ce5")
      (value "100n")
      (footprint "FP-CC0805-0_85-MFG")
      (description "CAP CER 0.1UF 25V X7R 0805")
      (fields (field (name "MANUFACTURER PART NUMBER") "CC0805KRX7R8BB104") (field (name "TOLERANCE") "0.1"))
      (libsource (lib "Altium Content Vault") (part "11868f565c42a9108669ba33697ecf6"))
    )
    (comp (ref "Ce6")
      (value "100n")
      (footprint "FP-CC0805-0_85-MFG")
      (description "CAP CER 0.1UF 25V X7R 0805")
      (fields (field (name "MANUFACTURER PART NUMBER") "CC0805KRX7R8BB104") (field (name "TOLERANCE") "0.1"))
      (libsource (lib "Altium Content Vault") (part "11868f565c42a9108669ba33697ecf6"))
    )
    (comp (ref "Ce7")
      (value "100n")
      (footprint "FP-CC0805-0_85-MFG")
      (description "CAP CER 0.1UF 25V X7R 0805")
      (fields (field (name "MANUFACTURER PART NUMBER") "CC0805KRX7R8BB104") (field (name "TOLERANCE") "0.1"))
      (libsource (lib "Altium Content Vault") (part "11868f565c42a9108669ba33697ecf6"))
    )
    (comp (ref "Ce8")
      (value "100n")
      (footprint "FP-CC0805-0_85-MFG")
      (description "CAP CER 0.1UF 25V X7R 0805")
      (fields (field (name "MANUFACTURER PART NUMBER") "CC0805KRX7R8BB104") (field (name "TOLERANCE") "0.1"))
      (libsource (lib "Altium Content Vault") (part "11868f565c42a9108669ba33697ecf6"))
    )
    (comp (ref "Ce9")
      (value "100n")
      (footprint "FP-CC0805-0_85-MFG")
      (description "CAP CER 0.1UF 25V X7R 0805")
      (fields (field (name "MANUFACTURER PART NUMBER") "CC0805KRX7R8BB104") (field (name "TOLERANCE") "0.1"))
      (libsource (lib "Altium Content Vault") (part "11868f565c42a9108669ba33697ecf6"))
    )
    (comp (ref "Ce10")
      (value "100n")
      (footprint "FP-CC0805-0_85-MFG")
      (description "CAP CER 0.1UF 25V X7R 0805")
      (fields (field (name "MANUFACTURER PART NUMBER") "CC0805KRX7R8BB104") (field (name "TOLERANCE") "0.1"))
      (libsource (lib "Altium Content Vault") (part "11868f565c42a9108669ba33697ecf6"))
    )
    (comp (ref "Ce11")
      (value "100n")
      (footprint "FP-CC0805-0_85-MFG")
      (description "CAP CER 0.1UF 25V X7R 0805")
      (fields (field (name "MANUFACTURER PART NUMBER") "CC0805KRX7R8BB104") (field (name "TOLERANCE") "0.1"))
      (libsource (lib "Altium Content Vault") (part "11868f565c42a9108669ba33697ecf6"))
    )
    (comp (ref "Ce12")
      (value "100n")
      (footprint "FP-CC0805-0_85-MFG")
      (description "CAP CER 0.1UF 25V X7R 0805")
      (fields (field (name "MANUFACTURER PART NUMBER") "CC0805KRX7R8BB104") (field (name "TOLERANCE") "0.1"))
      (libsource (lib "Altium Content Vault") (part "11868f565c42a9108669ba33697ecf6"))
    )
    (comp (ref "Ce13")
      (value "100n")
      (footprint "FP-CC0805-0_85-MFG")
      (description "CAP CER 0.1UF 25V X7R 0805")
      (fields (field (name "MANUFACTURER PART NUMBER") "CC0805KRX7R8BB104") (field (name "TOLERANCE") "0.1"))
      (libsource (lib "Altium Content Vault") (part "11868f565c42a9108669ba33697ecf6"))
    )
    (comp (ref "Ce14")
      (value "100n")
      (footprint "FP-CC0805-0_85-MFG")
      (description "CAP CER 0.1UF 25V X7R 0805")
      (fields (field (name "MANUFACTURER PART NUMBER") "CC0805KRX7R8BB104") (field (name "TOLERANCE") "0.1"))
      (libsource (lib "Altium Content Vault") (part "11868f565c42a9108669ba33697ecf6"))
    )
    (comp (ref "Ce15")
      (value "100n")
      (footprint "FP-CC0805-0_85-MFG")
      (description "CAP CER 0.1UF 25V X7R 0805")
      (fields (field (name "MANUFACTURER PART NUMBER") "CC0805KRX7R8BB104") (field (name "TOLERANCE") "0.1"))
      (libsource (lib "Altium Content Vault") (part "11868f565c42a9108669ba33697ecf6"))
    )
    (comp (ref "Ce16")
      (value "100n")
      (footprint "FP-CC0805-0_85-MFG")
      (description "CAP CER 0.1UF 25V X7R 0805")
      (fields (field (name "MANUFACTURER PART NUMBER") "CC0805KRX7R8BB104") (field (name "TOLERANCE") "0.1"))
      (libsource (lib "Altium Content Vault") (part "11868f565c42a9108669ba33697ecf6"))
    )
    (comp (ref "Ce17")
      (value "100n")
      (footprint "FP-CC0805-0_85-MFG")
      (description "CAP CER 0.1UF 25V X7R 0805")
      (fields (field (name "MANUFACTURER PART NUMBER") "CC0805KRX7R8BB104") (field (name "TOLERANCE") "0.1"))
      (libsource (lib "Altium Content Vault") (part "11868f565c42a9108669ba33697ecf6"))
    )
    (comp (ref "Ce18")
      (value "100n")
      (footprint "FP-CC0805-0_85-MFG")
      (description "CAP CER 0.1UF 25V X7R 0805")
      (fields (field (name "MANUFACTURER PART NUMBER") "CC0805KRX7R8BB104") (field (name "TOLERANCE") "0.1"))
      (libsource (lib "Altium Content Vault") (part "11868f565c42a9108669ba33697ecf6"))
    )
    (comp (ref "Ce19")
      (value "100n")
      (footprint "FP-CC0805-0_85-MFG")
      (description "CAP CER 0.1UF 25V X7R 0805")
      (fields (field (name "MANUFACTURER PART NUMBER") "CC0805KRX7R8BB104") (field (name "TOLERANCE") "0.1"))
      (libsource (lib "Altium Content Vault") (part "11868f565c42a9108669ba33697ecf6"))
    )
    (comp (ref "Ce20")
      (value "100n")
      (footprint "FP-CC0805-0_85-MFG")
      (description "CAP CER 0.1UF 25V X7R 0805")
      (fields (field (name "MANUFACTURER PART NUMBER") "CC0805KRX7R8BB104") (field (name "TOLERANCE") "0.1"))
      (libsource (lib "Altium Content Vault") (part "11868f565c42a9108669ba33697ecf6"))
    )
    (comp (ref "Cin+")
      (value "100n")
      (footprint "FP-CC0805-0_85-MFG")
      (description "CAP CER 0.1UF 25V X7R 0805")
      (fields (field (name "MANUFACTURER PART NUMBER") "CC0805KRX7R8BB104") (field (name "TOLERANCE") "0.1"))
      (libsource (lib "Altium Content Vault") (part "11868f565c42a9108669ba33697ecf6"))
    )
    (comp (ref "Cin-")
      (value "100n")
      (footprint "FP-CC0805-0_85-MFG")
      (description "CAP CER 0.1UF 25V X7R 0805")
      (fields (field (name "MANUFACTURER PART NUMBER") "CC0805KRX7R8BB104") (field (name "TOLERANCE") "0.1"))
      (libsource (lib "Altium Content Vault") (part "11868f565c42a9108669ba33697ecf6"))
    )
    (comp (ref "Cout+")
      (value "10u")
      (footprint "RAHV1100M1UCC8002E-Footprint-1")
      (libsource (lib "Li-Ren Liu") (part "CAP-NP-2"))
    )
    (comp (ref "Cout-")
      (value "10u")
      (footprint "RAHV1100M1UCC8002E-Footprint-1")
      (libsource (lib "Li-Ren Liu") (part "CAP-NP-2"))
    )
    (comp (ref "D1+")
      (value "1N4004RLG")
      (footprint "ONSC-AXIAL_LEAD-2-59-10_P")
      (description "Standard Recovery Rectifier, 2-Pin Axial_Lead, Pb-Free, Tape and Reel")
      (fields (field (name "MANUFACTURER") "On Semiconductor"))
      (libsource (lib "") (part "ONSC-D-K1A2-2_A_1"))
    )
    (comp (ref "D1-")
      (value "1N4004RLG")
      (footprint "ONSC-AXIAL_LEAD-2-59-10_P")
      (description "Standard Recovery Rectifier, 2-Pin Axial_Lead, Pb-Free, Tape and Reel")
      (fields (field (name "MANUFACTURER") "On Semiconductor"))
      (libsource (lib "") (part "ONSC-D-K1A2-2_A_2"))
    )
    (comp (ref "D2+")
      (value "1N4004RLG")
      (footprint "ONSC-AXIAL_LEAD-2-59-10_P")
      (description "Standard Recovery Rectifier, 2-Pin Axial_Lead, Pb-Free, Tape and Reel")
      (fields (field (name "MANUFACTURER") "On Semiconductor"))
      (libsource (lib "Altium Content Vault") (part "ONSC-D-K1A2-2_A"))
    )
    (comp (ref "D2-")
      (value "1N4004RLG")
      (footprint "ONSC-AXIAL_LEAD-2-59-10_P")
      (description "Standard Recovery Rectifier, 2-Pin Axial_Lead, Pb-Free, Tape and Reel")
      (fields (field (name "MANUFACTURER") "On Semiconductor"))
      (libsource (lib "") (part "ONSC-D-K1A2-2_A_3"))
    )
    (comp (ref "J1")
      (value "SMA Connector Female")
      (footprint "SMA_Smaller")
      (description "Our smaller SMA Female Connector purchased from amazon.com")
      (libsource (lib "Li-Ren Liu") (part "SMA-CONN"))
    )
    (comp (ref "J3")
      (value "SMA Connector Female")
      (footprint "SMA_Smaller")
      (description "Our smaller SMA Female Connector purchased from amazon.com")
      (libsource (lib "Li-Ren Liu") (part "SMA-CONN"))
    )
    (comp (ref "J8")
      (value "SMA Connector Female")
      (footprint "SMA_Smaller")
      (description "Our smaller SMA Female Connector purchased from amazon.com")
      (libsource (lib "Li-Ren Liu") (part "SMA-CONN"))
    )
    (comp (ref "J10")
      (value "SMA Connector Female")
      (footprint "SMA_Smaller")
      (description "Our smaller SMA Female Connector purchased from amazon.com")
      (libsource (lib "Li-Ren Liu") (part "SMA-CONN"))
    )
    (comp (ref "J12")
      (value "SMA Connector Female")
      (footprint "SMA_Smaller")
      (description "Our smaller SMA Female Connector purchased from amazon.com")
      (libsource (lib "Li-Ren Liu") (part "SMA-CONN"))
    )
    (comp (ref "J19")
      (value "SMA Connector Female")
      (footprint "SMA_Smaller")
      (description "Our smaller SMA Female Connector purchased from amazon.com")
      (libsource (lib "Li-Ren Liu") (part "SMA-CONN"))
    )
    (comp (ref "JIN")
      (value "1761028-4")
      (footprint "1761028-4-Footprint-1")
      (libsource (lib "Li-Ren Liu") (part "1761028-4-Symbol-1"))
    )
    (comp (ref "JOUT")
      (value "618025231121")
      (footprint "618025231121")
      (libsource (lib "Altium Content Vault") (part "D-Sub_Female_25p"))
    )
    (comp (ref "R1")
      (value "4.7k")
      (footprint "RESC2013X60X35NL10T20")
      (description "Chip Resistor, 47 KOhm, +/- 1%, 0.125 W, -55 to 155 degC, 0805 (2012 Metric), RoHS, Tape and Reel")
      (fields (field (name "MANUFACTURER") "Yageo"))
      (libsource (lib "Altium Content Vault") (part "RES-2"))
    )
    (comp (ref "R1+")
      (value "240")
      (footprint "RESC2013X60X35ML10T20")
      (description "Chip Resistor, 1 KOhm, +/- 1%, 125 mW, -55 to 155 degC, 0805 (2012 Metric), RoHS, Tape and Reel")
      (fields (field (name "TOLERANCE") "1%") (field (name "MANUFACTURER") "Yageo"))
      (libsource (lib "Altium Content Vault") (part "RES-2"))
    )
    (comp (ref "R1-")
      (value "240")
      (footprint "RESC2013X60X35ML10T20")
      (description "Chip Resistor, 1 KOhm, +/- 1%, 125 mW, -55 to 155 degC, 0805 (2012 Metric), RoHS, Tape and Reel")
      (fields (field (name "TOLERANCE") "1%") (field (name "MANUFACTURER") "Yageo"))
      (libsource (lib "Altium Content Vault") (part "RES-2"))
    )
    (comp (ref "R2")
      (value "4.7k")
      (footprint "RESC2013X60X35NL10T20")
      (description "Chip Resistor, 47 KOhm, +/- 1%, 0.125 W, -55 to 155 degC, 0805 (2012 Metric), RoHS, Tape and Reel")
      (fields (field (name "MANUFACTURER") "Yageo"))
      (libsource (lib "Altium Content Vault") (part "RES-2"))
    )
    (comp (ref "R2+")
      (value "5.1k")
      (footprint "RESC3216X60X45ML10T20")
      (fields (field (name "PART NUMBER") "CRCW1206680RFKEA") (field (name "MANUFACTURER") "Vishay Dale"))
      (libsource (lib "Altium Content Vault") (part "RES"))
    )
    (comp (ref "R2-")
      (value "5.1k")
      (footprint "RESC3216X60X45ML10T20")
      (fields (field (name "PART NUMBER") "CRCW1206680RFKEA") (field (name "MANUFACTURER") "Vishay Dale"))
      (libsource (lib "Altium Content Vault") (part "RES"))
    )
    (comp (ref "R3")
      (value "4.7k")
      (footprint "RESC2013X60X35NL10T20")
      (description "Chip Resistor, 47 KOhm, +/- 1%, 0.125 W, -55 to 155 degC, 0805 (2012 Metric), RoHS, Tape and Reel")
      (fields (field (name "MANUFACTURER") "Yageo"))
      (libsource (lib "Altium Content Vault") (part "RES-2"))
    )
    (comp (ref "R3+")
      (value "3.3k")
      (footprint "RESC3216X60X45ML10T20")
      (fields (field (name "PART NUMBER") "CRCW1206680RFKEA") (field (name "MANUFACTURER") "Vishay Dale"))
      (libsource (lib "Altium Content Vault") (part "RES"))
    )
    (comp (ref "R3-")
      (value "3.3k")
      (footprint "RESC3216X60X45ML10T20")
      (fields (field (name "PART NUMBER") "CRCW1206680RFKEA") (field (name "MANUFACTURER") "Vishay Dale"))
      (libsource (lib "Altium Content Vault") (part "RES"))
    )
    (comp (ref "R4")
      (value "4.7k")
      (footprint "RESC2013X60X35NL10T20")
      (description "Chip Resistor, 47 KOhm, +/- 1%, 0.125 W, -55 to 155 degC, 0805 (2012 Metric), RoHS, Tape and Reel")
      (fields (field (name "MANUFACTURER") "Yageo"))
      (libsource (lib "Altium Content Vault") (part "RES-2"))
    )
    (comp (ref "R5")
      (value "4.7k")
      (footprint "RESC2013X60X35NL10T20")
      (description "Chip Resistor, 47 KOhm, +/- 1%, 0.125 W, -55 to 155 degC, 0805 (2012 Metric), RoHS, Tape and Reel")
      (fields (field (name "MANUFACTURER") "Yageo"))
      (libsource (lib "Altium Content Vault") (part "RES-2"))
    )
    (comp (ref "R6")
      (value "4.7k")
      (footprint "RESC2013X60X35NL10T20")
      (description "Chip Resistor, 47 KOhm, +/- 1%, 0.125 W, -55 to 155 degC, 0805 (2012 Metric), RoHS, Tape and Reel")
      (fields (field (name "MANUFACTURER") "Yageo"))
      (libsource (lib "Altium Content Vault") (part "RES-2"))
    )
    (comp (ref "R7")
      (value "4.7k")
      (footprint "RESC2013X60X35NL10T20")
      (description "Chip Resistor, 47 KOhm, +/- 1%, 0.125 W, -55 to 155 degC, 0805 (2012 Metric), RoHS, Tape and Reel")
      (fields (field (name "MANUFACTURER") "Yageo"))
      (libsource (lib "Altium Content Vault") (part "RES-2"))
    )
    (comp (ref "R8")
      (value "4.7k")
      (footprint "RESC2013X60X35NL10T20")
      (description "Chip Resistor, 47 KOhm, +/- 1%, 0.125 W, -55 to 155 degC, 0805 (2012 Metric), RoHS, Tape and Reel")
      (fields (field (name "MANUFACTURER") "Yageo"))
      (libsource (lib "Altium Content Vault") (part "RES-2"))
    )
    (comp (ref "R9")
      (value "4.7k")
      (footprint "RESC2013X60X35NL10T20")
      (description "Chip Resistor, 47 KOhm, +/- 1%, 0.125 W, -55 to 155 degC, 0805 (2012 Metric), RoHS, Tape and Reel")
      (fields (field (name "MANUFACTURER") "Yageo"))
      (libsource (lib "Altium Content Vault") (part "RES-2"))
    )
    (comp (ref "R10")
      (value "4.7k")
      (footprint "RESC2013X60X35NL10T20")
      (description "Chip Resistor, 47 KOhm, +/- 1%, 0.125 W, -55 to 155 degC, 0805 (2012 Metric), RoHS, Tape and Reel")
      (fields (field (name "MANUFACTURER") "Yageo"))
      (libsource (lib "Altium Content Vault") (part "RES-2"))
    )
    (comp (ref "R11")
      (value "4.7k")
      (footprint "RESC2013X60X35NL10T20")
      (description "Chip Resistor, 47 KOhm, +/- 1%, 0.125 W, -55 to 155 degC, 0805 (2012 Metric), RoHS, Tape and Reel")
      (fields (field (name "MANUFACTURER") "Yageo"))
      (libsource (lib "Altium Content Vault") (part "RES-2"))
    )
    (comp (ref "R12")
      (value "4.7k")
      (footprint "RESC2013X60X35NL10T20")
      (description "Chip Resistor, 47 KOhm, +/- 1%, 0.125 W, -55 to 155 degC, 0805 (2012 Metric), RoHS, Tape and Reel")
      (fields (field (name "MANUFACTURER") "Yageo"))
      (libsource (lib "Altium Content Vault") (part "RES-2"))
    )
    (comp (ref "R13")
      (value "4.7k")
      (footprint "RESC2013X60X35NL10T20")
      (description "Chip Resistor, 47 KOhm, +/- 1%, 0.125 W, -55 to 155 degC, 0805 (2012 Metric), RoHS, Tape and Reel")
      (fields (field (name "MANUFACTURER") "Yageo"))
      (libsource (lib "Altium Content Vault") (part "RES-2"))
    )
    (comp (ref "R14")
      (value "4.7k")
      (footprint "RESC2013X60X35NL10T20")
      (description "Chip Resistor, 47 KOhm, +/- 1%, 0.125 W, -55 to 155 degC, 0805 (2012 Metric), RoHS, Tape and Reel")
      (fields (field (name "MANUFACTURER") "Yageo"))
      (libsource (lib "Altium Content Vault") (part "RES-2"))
    )
    (comp (ref "R15")
      (value "4.7k")
      (footprint "RESC2013X60X35NL10T20")
      (description "Chip Resistor, 47 KOhm, +/- 1%, 0.125 W, -55 to 155 degC, 0805 (2012 Metric), RoHS, Tape and Reel")
      (fields (field (name "MANUFACTURER") "Yageo"))
      (libsource (lib "Altium Content Vault") (part "RES-2"))
    )
    (comp (ref "R16")
      (value "4.7k")
      (footprint "RESC2013X60X35NL10T20")
      (description "Chip Resistor, 47 KOhm, +/- 1%, 0.125 W, -55 to 155 degC, 0805 (2012 Metric), RoHS, Tape and Reel")
      (fields (field (name "MANUFACTURER") "Yageo"))
      (libsource (lib "Altium Content Vault") (part "RES-2"))
    )
    (comp (ref "R17")
      (value "4.7k")
      (footprint "RESC2013X60X35NL10T20")
      (description "Chip Resistor, 47 KOhm, +/- 1%, 0.125 W, -55 to 155 degC, 0805 (2012 Metric), RoHS, Tape and Reel")
      (fields (field (name "MANUFACTURER") "Yageo"))
      (libsource (lib "Altium Content Vault") (part "RES-2"))
    )
    (comp (ref "R18")
      (value "4.7k")
      (footprint "RESC2013X60X35NL10T20")
      (description "Chip Resistor, 47 KOhm, +/- 1%, 0.125 W, -55 to 155 degC, 0805 (2012 Metric), RoHS, Tape and Reel")
      (fields (field (name "MANUFACTURER") "Yageo"))
      (libsource (lib "Altium Content Vault") (part "RES-2"))
    )
    (comp (ref "R19")
      (value "4.7k")
      (footprint "RESC2013X60X35NL10T20")
      (description "Chip Resistor, 47 KOhm, +/- 1%, 0.125 W, -55 to 155 degC, 0805 (2012 Metric), RoHS, Tape and Reel")
      (fields (field (name "MANUFACTURER") "Yageo"))
      (libsource (lib "Altium Content Vault") (part "RES-2"))
    )
    (comp (ref "R20")
      (value "4.7k")
      (footprint "RESC2013X60X35NL10T20")
      (description "Chip Resistor, 47 KOhm, +/- 1%, 0.125 W, -55 to 155 degC, 0805 (2012 Metric), RoHS, Tape and Reel")
      (fields (field (name "MANUFACTURER") "Yageo"))
      (libsource (lib "Altium Content Vault") (part "RES-2"))
    )
    (comp (ref "Re1")
      (value "10k")
      (footprint "RESC2013X60X35ML10T20")
      (description "Chip Resistor, 1 KOhm, +/- 1%, 125 mW, -55 to 155 degC, 0805 (2012 Metric), RoHS, Tape and Reel")
      (fields (field (name "TOLERANCE") "1%") (field (name "MANUFACTURER") "Yageo"))
      (libsource (lib "Altium Content Vault") (part "RES-2"))
    )
    (comp (ref "Re2")
      (value "10k")
      (footprint "RESC2013X60X35ML10T20")
      (description "Chip Resistor, 1 KOhm, +/- 1%, 125 mW, -55 to 155 degC, 0805 (2012 Metric), RoHS, Tape and Reel")
      (fields (field (name "TOLERANCE") "1%") (field (name "MANUFACTURER") "Yageo"))
      (libsource (lib "Altium Content Vault") (part "RES-2"))
    )
    (comp (ref "Re3")
      (value "10k")
      (footprint "RESC2013X60X35ML10T20")
      (description "Chip Resistor, 1 KOhm, +/- 1%, 125 mW, -55 to 155 degC, 0805 (2012 Metric), RoHS, Tape and Reel")
      (fields (field (name "TOLERANCE") "1%") (field (name "MANUFACTURER") "Yageo"))
      (libsource (lib "Altium Content Vault") (part "RES-2"))
    )
    (comp (ref "Re4")
      (value "10k")
      (footprint "RESC2013X60X35ML10T20")
      (description "Chip Resistor, 1 KOhm, +/- 1%, 125 mW, -55 to 155 degC, 0805 (2012 Metric), RoHS, Tape and Reel")
      (fields (field (name "TOLERANCE") "1%") (field (name "MANUFACTURER") "Yageo"))
      (libsource (lib "Altium Content Vault") (part "RES-2"))
    )
    (comp (ref "Re5")
      (value "10k")
      (footprint "RESC2013X60X35ML10T20")
      (description "Chip Resistor, 1 KOhm, +/- 1%, 125 mW, -55 to 155 degC, 0805 (2012 Metric), RoHS, Tape and Reel")
      (fields (field (name "TOLERANCE") "1%") (field (name "MANUFACTURER") "Yageo"))
      (libsource (lib "Altium Content Vault") (part "RES-2"))
    )
    (comp (ref "Re6")
      (value "10k")
      (footprint "RESC2013X60X35ML10T20")
      (description "Chip Resistor, 1 KOhm, +/- 1%, 125 mW, -55 to 155 degC, 0805 (2012 Metric), RoHS, Tape and Reel")
      (fields (field (name "TOLERANCE") "1%") (field (name "MANUFACTURER") "Yageo"))
      (libsource (lib "Altium Content Vault") (part "RES-2"))
    )
    (comp (ref "Re7")
      (value "10k")
      (footprint "RESC2013X60X35ML10T20")
      (description "Chip Resistor, 1 KOhm, +/- 1%, 125 mW, -55 to 155 degC, 0805 (2012 Metric), RoHS, Tape and Reel")
      (fields (field (name "TOLERANCE") "1%") (field (name "MANUFACTURER") "Yageo"))
      (libsource (lib "Altium Content Vault") (part "RES-2"))
    )
    (comp (ref "Re8")
      (value "10k")
      (footprint "RESC2013X60X35ML10T20")
      (description "Chip Resistor, 1 KOhm, +/- 1%, 125 mW, -55 to 155 degC, 0805 (2012 Metric), RoHS, Tape and Reel")
      (fields (field (name "TOLERANCE") "1%") (field (name "MANUFACTURER") "Yageo"))
      (libsource (lib "Altium Content Vault") (part "RES-2"))
    )
    (comp (ref "Re9")
      (value "10k")
      (footprint "RESC2013X60X35ML10T20")
      (description "Chip Resistor, 1 KOhm, +/- 1%, 125 mW, -55 to 155 degC, 0805 (2012 Metric), RoHS, Tape and Reel")
      (fields (field (name "TOLERANCE") "1%") (field (name "MANUFACTURER") "Yageo"))
      (libsource (lib "Altium Content Vault") (part "RES-2"))
    )
    (comp (ref "Re10")
      (value "10k")
      (footprint "RESC2013X60X35ML10T20")
      (description "Chip Resistor, 1 KOhm, +/- 1%, 125 mW, -55 to 155 degC, 0805 (2012 Metric), RoHS, Tape and Reel")
      (fields (field (name "TOLERANCE") "1%") (field (name "MANUFACTURER") "Yageo"))
      (libsource (lib "Altium Content Vault") (part "RES-2"))
    )
    (comp (ref "Re11")
      (value "10k")
      (footprint "RESC2013X60X35ML10T20")
      (description "Chip Resistor, 1 KOhm, +/- 1%, 125 mW, -55 to 155 degC, 0805 (2012 Metric), RoHS, Tape and Reel")
      (fields (field (name "TOLERANCE") "1%") (field (name "MANUFACTURER") "Yageo"))
      (libsource (lib "Altium Content Vault") (part "RES-2"))
    )
    (comp (ref "Re12")
      (value "10k")
      (footprint "RESC2013X60X35ML10T20")
      (description "Chip Resistor, 1 KOhm, +/- 1%, 125 mW, -55 to 155 degC, 0805 (2012 Metric), RoHS, Tape and Reel")
      (fields (field (name "TOLERANCE") "1%") (field (name "MANUFACTURER") "Yageo"))
      (libsource (lib "Altium Content Vault") (part "RES-2"))
    )
    (comp (ref "Re13")
      (value "10k")
      (footprint "RESC2013X60X35ML10T20")
      (description "Chip Resistor, 1 KOhm, +/- 1%, 125 mW, -55 to 155 degC, 0805 (2012 Metric), RoHS, Tape and Reel")
      (fields (field (name "TOLERANCE") "1%") (field (name "MANUFACTURER") "Yageo"))
      (libsource (lib "Altium Content Vault") (part "RES-2"))
    )
    (comp (ref "Re14")
      (value "10k")
      (footprint "RESC2013X60X35ML10T20")
      (description "Chip Resistor, 1 KOhm, +/- 1%, 125 mW, -55 to 155 degC, 0805 (2012 Metric), RoHS, Tape and Reel")
      (fields (field (name "TOLERANCE") "1%") (field (name "MANUFACTURER") "Yageo"))
      (libsource (lib "Altium Content Vault") (part "RES-2"))
    )
    (comp (ref "Re15")
      (value "10k")
      (footprint "RESC2013X60X35ML10T20")
      (description "Chip Resistor, 1 KOhm, +/- 1%, 125 mW, -55 to 155 degC, 0805 (2012 Metric), RoHS, Tape and Reel")
      (fields (field (name "TOLERANCE") "1%") (field (name "MANUFACTURER") "Yageo"))
      (libsource (lib "Altium Content Vault") (part "RES-2"))
    )
    (comp (ref "Re16")
      (value "10k")
      (footprint "RESC2013X60X35ML10T20")
      (description "Chip Resistor, 1 KOhm, +/- 1%, 125 mW, -55 to 155 degC, 0805 (2012 Metric), RoHS, Tape and Reel")
      (fields (field (name "TOLERANCE") "1%") (field (name "MANUFACTURER") "Yageo"))
      (libsource (lib "Altium Content Vault") (part "RES-2"))
    )
    (comp (ref "Re17")
      (value "10k")
      (footprint "RESC2013X60X35ML10T20")
      (description "Chip Resistor, 1 KOhm, +/- 1%, 125 mW, -55 to 155 degC, 0805 (2012 Metric), RoHS, Tape and Reel")
      (fields (field (name "TOLERANCE") "1%") (field (name "MANUFACTURER") "Yageo"))
      (libsource (lib "Altium Content Vault") (part "RES-2"))
    )
    (comp (ref "Re18")
      (value "10k")
      (footprint "RESC2013X60X35ML10T20")
      (description "Chip Resistor, 1 KOhm, +/- 1%, 125 mW, -55 to 155 degC, 0805 (2012 Metric), RoHS, Tape and Reel")
      (fields (field (name "TOLERANCE") "1%") (field (name "MANUFACTURER") "Yageo"))
      (libsource (lib "Altium Content Vault") (part "RES-2"))
    )
    (comp (ref "Re19")
      (value "10k")
      (footprint "RESC2013X60X35ML10T20")
      (description "Chip Resistor, 1 KOhm, +/- 1%, 125 mW, -55 to 155 degC, 0805 (2012 Metric), RoHS, Tape and Reel")
      (fields (field (name "TOLERANCE") "1%") (field (name "MANUFACTURER") "Yageo"))
      (libsource (lib "Altium Content Vault") (part "RES-2"))
    )
    (comp (ref "Re20")
      (value "10k")
      (footprint "RESC2013X60X35ML10T20")
      (description "Chip Resistor, 1 KOhm, +/- 1%, 125 mW, -55 to 155 degC, 0805 (2012 Metric), RoHS, Tape and Reel")
      (fields (field (name "TOLERANCE") "1%") (field (name "MANUFACTURER") "Yageo"))
      (libsource (lib "Altium Content Vault") (part "RES-2"))
    )
    (comp (ref "Rf1")
      (value "33k")
      (footprint "RESC2013X60X35ML10T20")
      (description "Chip Resistor, 3.3 KOhm, +/- 1%, 0.125 W, -55 to 155 degC, 0805 (2012 Metric), RoHS, Tape and Reel")
      (fields (field (name "TOLERANCE") "1%") (field (name "MANUFACTURER") "Yageo"))
      (libsource (lib "Altium Content Vault") (part "RES-2"))
    )
    (comp (ref "Rf2")
      (value "33k")
      (footprint "RESC2013X60X35ML10T20")
      (description "Chip Resistor, 3.3 KOhm, +/- 1%, 0.125 W, -55 to 155 degC, 0805 (2012 Metric), RoHS, Tape and Reel")
      (fields (field (name "TOLERANCE") "1%") (field (name "MANUFACTURER") "Yageo"))
      (libsource (lib "Altium Content Vault") (part "RES-2"))
    )
    (comp (ref "Rf3")
      (value "33k")
      (footprint "RESC2013X60X35ML10T20")
      (description "Chip Resistor, 3.3 KOhm, +/- 1%, 0.125 W, -55 to 155 degC, 0805 (2012 Metric), RoHS, Tape and Reel")
      (fields (field (name "TOLERANCE") "1%") (field (name "MANUFACTURER") "Yageo"))
      (libsource (lib "Altium Content Vault") (part "RES-2"))
    )
    (comp (ref "Rf4")
      (value "33k")
      (footprint "RESC2013X60X35ML10T20")
      (description "Chip Resistor, 3.3 KOhm, +/- 1%, 0.125 W, -55 to 155 degC, 0805 (2012 Metric), RoHS, Tape and Reel")
      (fields (field (name "TOLERANCE") "1%") (field (name "MANUFACTURER") "Yageo"))
      (libsource (lib "Altium Content Vault") (part "RES-2"))
    )
    (comp (ref "Rf5")
      (value "33k")
      (footprint "RESC2013X60X35ML10T20")
      (description "Chip Resistor, 3.3 KOhm, +/- 1%, 0.125 W, -55 to 155 degC, 0805 (2012 Metric), RoHS, Tape and Reel")
      (fields (field (name "TOLERANCE") "1%") (field (name "MANUFACTURER") "Yageo"))
      (libsource (lib "Altium Content Vault") (part "RES-2"))
    )
    (comp (ref "Rf6")
      (value "33k")
      (footprint "RESC2013X60X35ML10T20")
      (description "Chip Resistor, 3.3 KOhm, +/- 1%, 0.125 W, -55 to 155 degC, 0805 (2012 Metric), RoHS, Tape and Reel")
      (fields (field (name "TOLERANCE") "1%") (field (name "MANUFACTURER") "Yageo"))
      (libsource (lib "Altium Content Vault") (part "RES-2"))
    )
    (comp (ref "Rf7")
      (value "33k")
      (footprint "RESC2013X60X35ML10T20")
      (description "Chip Resistor, 3.3 KOhm, +/- 1%, 0.125 W, -55 to 155 degC, 0805 (2012 Metric), RoHS, Tape and Reel")
      (fields (field (name "TOLERANCE") "1%") (field (name "MANUFACTURER") "Yageo"))
      (libsource (lib "Altium Content Vault") (part "RES-2"))
    )
    (comp (ref "Rf8")
      (value "33k")
      (footprint "RESC2013X60X35ML10T20")
      (description "Chip Resistor, 3.3 KOhm, +/- 1%, 0.125 W, -55 to 155 degC, 0805 (2012 Metric), RoHS, Tape and Reel")
      (fields (field (name "TOLERANCE") "1%") (field (name "MANUFACTURER") "Yageo"))
      (libsource (lib "Altium Content Vault") (part "RES-2"))
    )
    (comp (ref "Rf9")
      (value "33k")
      (footprint "RESC2013X60X35ML10T20")
      (description "Chip Resistor, 3.3 KOhm, +/- 1%, 0.125 W, -55 to 155 degC, 0805 (2012 Metric), RoHS, Tape and Reel")
      (fields (field (name "TOLERANCE") "1%") (field (name "MANUFACTURER") "Yageo"))
      (libsource (lib "Altium Content Vault") (part "RES-2"))
    )
    (comp (ref "Rf10")
      (value "33k")
      (footprint "RESC2013X60X35ML10T20")
      (description "Chip Resistor, 3.3 KOhm, +/- 1%, 0.125 W, -55 to 155 degC, 0805 (2012 Metric), RoHS, Tape and Reel")
      (fields (field (name "TOLERANCE") "1%") (field (name "MANUFACTURER") "Yageo"))
      (libsource (lib "Altium Content Vault") (part "RES-2"))
    )
    (comp (ref "Rf11")
      (value "33k")
      (footprint "RESC2013X60X35ML10T20")
      (description "Chip Resistor, 3.3 KOhm, +/- 1%, 0.125 W, -55 to 155 degC, 0805 (2012 Metric), RoHS, Tape and Reel")
      (fields (field (name "TOLERANCE") "1%") (field (name "MANUFACTURER") "Yageo"))
      (libsource (lib "Altium Content Vault") (part "RES-2"))
    )
    (comp (ref "Rf12")
      (value "33k")
      (footprint "RESC2013X60X35ML10T20")
      (description "Chip Resistor, 3.3 KOhm, +/- 1%, 0.125 W, -55 to 155 degC, 0805 (2012 Metric), RoHS, Tape and Reel")
      (fields (field (name "TOLERANCE") "1%") (field (name "MANUFACTURER") "Yageo"))
      (libsource (lib "Altium Content Vault") (part "RES-2"))
    )
    (comp (ref "Rf13")
      (value "33k")
      (footprint "RESC2013X60X35ML10T20")
      (description "Chip Resistor, 3.3 KOhm, +/- 1%, 0.125 W, -55 to 155 degC, 0805 (2012 Metric), RoHS, Tape and Reel")
      (fields (field (name "TOLERANCE") "1%") (field (name "MANUFACTURER") "Yageo"))
      (libsource (lib "Altium Content Vault") (part "RES-2"))
    )
    (comp (ref "Rf14")
      (value "33k")
      (footprint "RESC2013X60X35ML10T20")
      (description "Chip Resistor, 3.3 KOhm, +/- 1%, 0.125 W, -55 to 155 degC, 0805 (2012 Metric), RoHS, Tape and Reel")
      (fields (field (name "TOLERANCE") "1%") (field (name "MANUFACTURER") "Yageo"))
      (libsource (lib "Altium Content Vault") (part "RES-2"))
    )
    (comp (ref "Rf15")
      (value "33k")
      (footprint "RESC2013X60X35ML10T20")
      (description "Chip Resistor, 3.3 KOhm, +/- 1%, 0.125 W, -55 to 155 degC, 0805 (2012 Metric), RoHS, Tape and Reel")
      (fields (field (name "TOLERANCE") "1%") (field (name "MANUFACTURER") "Yageo"))
      (libsource (lib "Altium Content Vault") (part "RES-2"))
    )
    (comp (ref "Rf16")
      (value "33k")
      (footprint "RESC2013X60X35ML10T20")
      (description "Chip Resistor, 3.3 KOhm, +/- 1%, 0.125 W, -55 to 155 degC, 0805 (2012 Metric), RoHS, Tape and Reel")
      (fields (field (name "TOLERANCE") "1%") (field (name "MANUFACTURER") "Yageo"))
      (libsource (lib "Altium Content Vault") (part "RES-2"))
    )
    (comp (ref "Rf17")
      (value "33k")
      (footprint "RESC2013X60X35ML10T20")
      (description "Chip Resistor, 3.3 KOhm, +/- 1%, 0.125 W, -55 to 155 degC, 0805 (2012 Metric), RoHS, Tape and Reel")
      (fields (field (name "TOLERANCE") "1%") (field (name "MANUFACTURER") "Yageo"))
      (libsource (lib "Altium Content Vault") (part "RES-2"))
    )
    (comp (ref "Rf18")
      (value "33k")
      (footprint "RESC2013X60X35ML10T20")
      (description "Chip Resistor, 3.3 KOhm, +/- 1%, 0.125 W, -55 to 155 degC, 0805 (2012 Metric), RoHS, Tape and Reel")
      (fields (field (name "TOLERANCE") "1%") (field (name "MANUFACTURER") "Yageo"))
      (libsource (lib "Altium Content Vault") (part "RES-2"))
    )
    (comp (ref "Rf19")
      (value "33k")
      (footprint "RESC2013X60X35ML10T20")
      (description "Chip Resistor, 3.3 KOhm, +/- 1%, 0.125 W, -55 to 155 degC, 0805 (2012 Metric), RoHS, Tape and Reel")
      (fields (field (name "TOLERANCE") "1%") (field (name "MANUFACTURER") "Yageo"))
      (libsource (lib "Altium Content Vault") (part "RES-2"))
    )
    (comp (ref "Rf20")
      (value "33k")
      (footprint "RESC2013X60X35ML10T20")
      (description "Chip Resistor, 3.3 KOhm, +/- 1%, 0.125 W, -55 to 155 degC, 0805 (2012 Metric), RoHS, Tape and Reel")
      (fields (field (name "TOLERANCE") "1%") (field (name "MANUFACTURER") "Yageo"))
      (libsource (lib "Altium Content Vault") (part "RES-2"))
    )
    (comp (ref "Rg1")
      (value "10k")
      (footprint "RESC2013X60X35ML10T20")
      (description "Chip Resistor, 1 KOhm, +/- 1%, 125 mW, -55 to 155 degC, 0805 (2012 Metric), RoHS, Tape and Reel")
      (fields (field (name "TOLERANCE") "1%") (field (name "MANUFACTURER") "Yageo"))
      (libsource (lib "Altium Content Vault") (part "RES-2"))
    )
    (comp (ref "Rg2")
      (value "10k")
      (footprint "RESC2013X60X35ML10T20")
      (description "Chip Resistor, 1 KOhm, +/- 1%, 125 mW, -55 to 155 degC, 0805 (2012 Metric), RoHS, Tape and Reel")
      (fields (field (name "TOLERANCE") "1%") (field (name "MANUFACTURER") "Yageo"))
      (libsource (lib "Altium Content Vault") (part "RES-2"))
    )
    (comp (ref "Rg3")
      (value "10k")
      (footprint "RESC2013X60X35ML10T20")
      (description "Chip Resistor, 1 KOhm, +/- 1%, 125 mW, -55 to 155 degC, 0805 (2012 Metric), RoHS, Tape and Reel")
      (fields (field (name "TOLERANCE") "1%") (field (name "MANUFACTURER") "Yageo"))
      (libsource (lib "Altium Content Vault") (part "RES-2"))
    )
    (comp (ref "Rg4")
      (value "10k")
      (footprint "RESC2013X60X35ML10T20")
      (description "Chip Resistor, 1 KOhm, +/- 1%, 125 mW, -55 to 155 degC, 0805 (2012 Metric), RoHS, Tape and Reel")
      (fields (field (name "TOLERANCE") "1%") (field (name "MANUFACTURER") "Yageo"))
      (libsource (lib "Altium Content Vault") (part "RES-2"))
    )
    (comp (ref "Rg5")
      (value "10k")
      (footprint "RESC2013X60X35ML10T20")
      (description "Chip Resistor, 1 KOhm, +/- 1%, 125 mW, -55 to 155 degC, 0805 (2012 Metric), RoHS, Tape and Reel")
      (fields (field (name "TOLERANCE") "1%") (field (name "MANUFACTURER") "Yageo"))
      (libsource (lib "Altium Content Vault") (part "RES-2"))
    )
    (comp (ref "Rg6")
      (value "10k")
      (footprint "RESC2013X60X35ML10T20")
      (description "Chip Resistor, 1 KOhm, +/- 1%, 125 mW, -55 to 155 degC, 0805 (2012 Metric), RoHS, Tape and Reel")
      (fields (field (name "TOLERANCE") "1%") (field (name "MANUFACTURER") "Yageo"))
      (libsource (lib "Altium Content Vault") (part "RES-2"))
    )
    (comp (ref "Rg7")
      (value "10k")
      (footprint "RESC2013X60X35ML10T20")
      (description "Chip Resistor, 1 KOhm, +/- 1%, 125 mW, -55 to 155 degC, 0805 (2012 Metric), RoHS, Tape and Reel")
      (fields (field (name "TOLERANCE") "1%") (field (name "MANUFACTURER") "Yageo"))
      (libsource (lib "Altium Content Vault") (part "RES-2"))
    )
    (comp (ref "Rg8")
      (value "10k")
      (footprint "RESC2013X60X35ML10T20")
      (description "Chip Resistor, 1 KOhm, +/- 1%, 125 mW, -55 to 155 degC, 0805 (2012 Metric), RoHS, Tape and Reel")
      (fields (field (name "TOLERANCE") "1%") (field (name "MANUFACTURER") "Yageo"))
      (libsource (lib "Altium Content Vault") (part "RES-2"))
    )
    (comp (ref "Rg9")
      (value "10k")
      (footprint "RESC2013X60X35ML10T20")
      (description "Chip Resistor, 1 KOhm, +/- 1%, 125 mW, -55 to 155 degC, 0805 (2012 Metric), RoHS, Tape and Reel")
      (fields (field (name "TOLERANCE") "1%") (field (name "MANUFACTURER") "Yageo"))
      (libsource (lib "Altium Content Vault") (part "RES-2"))
    )
    (comp (ref "Rg10")
      (value "10k")
      (footprint "RESC2013X60X35ML10T20")
      (description "Chip Resistor, 1 KOhm, +/- 1%, 125 mW, -55 to 155 degC, 0805 (2012 Metric), RoHS, Tape and Reel")
      (fields (field (name "TOLERANCE") "1%") (field (name "MANUFACTURER") "Yageo"))
      (libsource (lib "Altium Content Vault") (part "RES-2"))
    )
    (comp (ref "Rg11")
      (value "10k")
      (footprint "RESC2013X60X35ML10T20")
      (description "Chip Resistor, 1 KOhm, +/- 1%, 125 mW, -55 to 155 degC, 0805 (2012 Metric), RoHS, Tape and Reel")
      (fields (field (name "TOLERANCE") "1%") (field (name "MANUFACTURER") "Yageo"))
      (libsource (lib "Altium Content Vault") (part "RES-2"))
    )
    (comp (ref "Rg12")
      (value "10k")
      (footprint "RESC2013X60X35ML10T20")
      (description "Chip Resistor, 1 KOhm, +/- 1%, 125 mW, -55 to 155 degC, 0805 (2012 Metric), RoHS, Tape and Reel")
      (fields (field (name "TOLERANCE") "1%") (field (name "MANUFACTURER") "Yageo"))
      (libsource (lib "Altium Content Vault") (part "RES-2"))
    )
    (comp (ref "Rg13")
      (value "10k")
      (footprint "RESC2013X60X35ML10T20")
      (description "Chip Resistor, 1 KOhm, +/- 1%, 125 mW, -55 to 155 degC, 0805 (2012 Metric), RoHS, Tape and Reel")
      (fields (field (name "TOLERANCE") "1%") (field (name "MANUFACTURER") "Yageo"))
      (libsource (lib "Altium Content Vault") (part "RES-2"))
    )
    (comp (ref "Rg14")
      (value "10k")
      (footprint "RESC2013X60X35ML10T20")
      (description "Chip Resistor, 1 KOhm, +/- 1%, 125 mW, -55 to 155 degC, 0805 (2012 Metric), RoHS, Tape and Reel")
      (fields (field (name "TOLERANCE") "1%") (field (name "MANUFACTURER") "Yageo"))
      (libsource (lib "Altium Content Vault") (part "RES-2"))
    )
    (comp (ref "Rg15")
      (value "10k")
      (footprint "RESC2013X60X35ML10T20")
      (description "Chip Resistor, 1 KOhm, +/- 1%, 125 mW, -55 to 155 degC, 0805 (2012 Metric), RoHS, Tape and Reel")
      (fields (field (name "TOLERANCE") "1%") (field (name "MANUFACTURER") "Yageo"))
      (libsource (lib "Altium Content Vault") (part "RES-2"))
    )
    (comp (ref "Rg16")
      (value "10k")
      (footprint "RESC2013X60X35ML10T20")
      (description "Chip Resistor, 1 KOhm, +/- 1%, 125 mW, -55 to 155 degC, 0805 (2012 Metric), RoHS, Tape and Reel")
      (fields (field (name "TOLERANCE") "1%") (field (name "MANUFACTURER") "Yageo"))
      (libsource (lib "Altium Content Vault") (part "RES-2"))
    )
    (comp (ref "Rg17")
      (value "10k")
      (footprint "RESC2013X60X35ML10T20")
      (description "Chip Resistor, 1 KOhm, +/- 1%, 125 mW, -55 to 155 degC, 0805 (2012 Metric), RoHS, Tape and Reel")
      (fields (field (name "TOLERANCE") "1%") (field (name "MANUFACTURER") "Yageo"))
      (libsource (lib "Altium Content Vault") (part "RES-2"))
    )
    (comp (ref "Rg18")
      (value "10k")
      (footprint "RESC2013X60X35ML10T20")
      (description "Chip Resistor, 1 KOhm, +/- 1%, 125 mW, -55 to 155 degC, 0805 (2012 Metric), RoHS, Tape and Reel")
      (fields (field (name "TOLERANCE") "1%") (field (name "MANUFACTURER") "Yageo"))
      (libsource (lib "Altium Content Vault") (part "RES-2"))
    )
    (comp (ref "Rg19")
      (value "10k")
      (footprint "RESC2013X60X35ML10T20")
      (description "Chip Resistor, 1 KOhm, +/- 1%, 125 mW, -55 to 155 degC, 0805 (2012 Metric), RoHS, Tape and Reel")
      (fields (field (name "TOLERANCE") "1%") (field (name "MANUFACTURER") "Yageo"))
      (libsource (lib "Altium Content Vault") (part "RES-2"))
    )
    (comp (ref "Rg20")
      (value "10k")
      (footprint "RESC2013X60X35ML10T20")
      (description "Chip Resistor, 1 KOhm, +/- 1%, 125 mW, -55 to 155 degC, 0805 (2012 Metric), RoHS, Tape and Reel")
      (fields (field (name "TOLERANCE") "1%") (field (name "MANUFACTURER") "Yageo"))
      (libsource (lib "Altium Content Vault") (part "RES-2"))
    )
    (comp (ref "T1")
      (value "PBTC-1GW+")
      (footprint "PBTC-1GW+")
      (description "Mini-Circuit Bias-Tee (Version 2)")
      (libsource (lib "Li-Ren Liu") (part "PBTC-1GW+"))
    )
    (comp (ref "T3")
      (value "PBTC-1GW+")
      (footprint "PBTC-1GW+")
      (description "Mini-Circuit Bias-Tee (Version 2)")
      (libsource (lib "Li-Ren Liu") (part "PBTC-1GW+"))
    )
    (comp (ref "T8")
      (value "PBTC-1GW+")
      (footprint "PBTC-1GW+")
      (description "Mini-Circuit Bias-Tee (Version 2)")
      (libsource (lib "Li-Ren Liu") (part "PBTC-1GW+"))
    )
    (comp (ref "T10")
      (value "PBTC-1GW+")
      (footprint "PBTC-1GW+")
      (description "Mini-Circuit Bias-Tee (Version 2)")
      (libsource (lib "Li-Ren Liu") (part "PBTC-1GW+"))
    )
    (comp (ref "T12")
      (value "PBTC-1GW+")
      (footprint "PBTC-1GW+")
      (description "Mini-Circuit Bias-Tee (Version 2)")
      (libsource (lib "Li-Ren Liu") (part "PBTC-1GW+"))
    )
    (comp (ref "T19")
      (value "PBTC-1GW+")
      (footprint "PBTC-1GW+")
      (description "Mini-Circuit Bias-Tee (Version 2)")
      (libsource (lib "Li-Ren Liu") (part "PBTC-1GW+"))
    )
    (comp (ref "U+")
      (value "LM317T")
      (footprint "TO-220")
      (description "1.5A, 1.2V to 37V Adjustable Voltage Regulator, 3-Pin TO-220")
      (libsource (lib "Altium Content Vault") (part "PM-REG-117-SIL3"))
    )
    (comp (ref "U-")
      (value "LM337SP")
      (footprint "TO220")
      (description "Three-Terminal Negative Voltage Regulator, 3-Pin TO-220")
      (libsource (lib "Altium Content Vault") (part "PM-REG-117-CY3"))
    )
    (comp (ref "U1")
      (value "OPA454AIDDA")
      (footprint "DDA0008C_L")
      (fields (field (name "MANUFACTURER") "Texas Instruments"))
      (libsource (lib "Altium Content Vault") (part "TI-OPA454-DDA8"))
    )
    (comp (ref "U2")
      (value "OPA454AIDDA")
      (footprint "DDA0008C_L")
      (fields (field (name "MANUFACTURER") "Texas Instruments"))
      (libsource (lib "Altium Content Vault") (part "TI-OPA454-DDA8"))
    )
    (comp (ref "U3")
      (value "OPA454AIDDA")
      (footprint "DDA0008C_L")
      (fields (field (name "MANUFACTURER") "Texas Instruments"))
      (libsource (lib "Altium Content Vault") (part "TI-OPA454-DDA8"))
    )
    (comp (ref "U4")
      (value "OPA454AIDDA")
      (footprint "DDA0008C_L")
      (fields (field (name "MANUFACTURER") "Texas Instruments"))
      (libsource (lib "Altium Content Vault") (part "TI-OPA454-DDA8"))
    )
    (comp (ref "U5")
      (value "OPA454AIDDA")
      (footprint "DDA0008C_L")
      (fields (field (name "MANUFACTURER") "Texas Instruments"))
      (libsource (lib "Altium Content Vault") (part "TI-OPA454-DDA8"))
    )
    (comp (ref "U6")
      (value "OPA454AIDDA")
      (footprint "DDA0008C_L")
      (fields (field (name "MANUFACTURER") "Texas Instruments"))
      (libsource (lib "Altium Content Vault") (part "TI-OPA454-DDA8"))
    )
    (comp (ref "U7")
      (value "OPA454AIDDA")
      (footprint "DDA0008C_L")
      (fields (field (name "MANUFACTURER") "Texas Instruments"))
      (libsource (lib "Altium Content Vault") (part "TI-OPA454-DDA8"))
    )
    (comp (ref "U8")
      (value "OPA454AIDDA")
      (footprint "DDA0008C_L")
      (fields (field (name "MANUFACTURER") "Texas Instruments"))
      (libsource (lib "Altium Content Vault") (part "TI-OPA454-DDA8"))
    )
    (comp (ref "U9")
      (value "OPA454AIDDA")
      (footprint "DDA0008C_L")
      (fields (field (name "MANUFACTURER") "Texas Instruments"))
      (libsource (lib "Altium Content Vault") (part "TI-OPA454-DDA8"))
    )
    (comp (ref "U10")
      (value "OPA454AIDDA")
      (footprint "DDA0008C_L")
      (fields (field (name "MANUFACTURER") "Texas Instruments"))
      (libsource (lib "Altium Content Vault") (part "TI-OPA454-DDA8"))
    )
    (comp (ref "U11")
      (value "OPA454AIDDA")
      (footprint "DDA0008C_L")
      (fields (field (name "MANUFACTURER") "Texas Instruments"))
      (libsource (lib "Altium Content Vault") (part "TI-OPA454-DDA8"))
    )
    (comp (ref "U12")
      (value "OPA454AIDDA")
      (footprint "DDA0008C_L")
      (fields (field (name "MANUFACTURER") "Texas Instruments"))
      (libsource (lib "Altium Content Vault") (part "TI-OPA454-DDA8"))
    )
    (comp (ref "U13")
      (value "OPA454AIDDA")
      (footprint "DDA0008C_L")
      (fields (field (name "MANUFACTURER") "Texas Instruments"))
      (libsource (lib "Altium Content Vault") (part "TI-OPA454-DDA8"))
    )
    (comp (ref "U14")
      (value "OPA454AIDDA")
      (footprint "DDA0008C_L")
      (fields (field (name "MANUFACTURER") "Texas Instruments"))
      (libsource (lib "Altium Content Vault") (part "TI-OPA454-DDA8"))
    )
    (comp (ref "U15")
      (value "OPA454AIDDA")
      (footprint "DDA0008C_L")
      (fields (field (name "MANUFACTURER") "Texas Instruments"))
      (libsource (lib "Altium Content Vault") (part "TI-OPA454-DDA8"))
    )
    (comp (ref "U16")
      (value "OPA454AIDDA")
      (footprint "DDA0008C_L")
      (fields (field (name "MANUFACTURER") "Texas Instruments"))
      (libsource (lib "Altium Content Vault") (part "TI-OPA454-DDA8"))
    )
    (comp (ref "U17")
      (value "OPA454AIDDA")
      (footprint "DDA0008C_L")
      (fields (field (name "MANUFACTURER") "Texas Instruments"))
      (libsource (lib "Altium Content Vault") (part "TI-OPA454-DDA8"))
    )
    (comp (ref "U18")
      (value "OPA454AIDDA")
      (footprint "DDA0008C_L")
      (fields (field (name "MANUFACTURER") "Texas Instruments"))
      (libsource (lib "Altium Content Vault") (part "TI-OPA454-DDA8"))
    )
    (comp (ref "U19")
      (value "OPA454AIDDA")
      (footprint "DDA0008C_L")
      (fields (field (name "MANUFACTURER") "Texas Instruments"))
      (libsource (lib "Altium Content Vault") (part "TI-OPA454-DDA8"))
    )
    (comp (ref "U20")
      (value "OPA454AIDDA")
      (footprint "DDA0008C_L")
      (fields (field (name "MANUFACTURER") "Texas Instruments"))
      (libsource (lib "Altium Content Vault") (part "TI-OPA454-DDA8"))
    )
  )
  (nets
    (net (code "1") (name "+5V") (class "Default")
      (node (ref "Ce1") (pin "2") (pinfunction "2_2") (pintype "passive"))
      (node (ref "Ce10") (pin "2") (pinfunction "2_2") (pintype "passive"))
      (node (ref "Ce11") (pin "2") (pinfunction "2_2") (pintype "passive"))
      (node (ref "Ce12") (pin "2") (pinfunction "2_2") (pintype "passive"))
      (node (ref "Ce13") (pin "2") (pinfunction "2_2") (pintype "passive"))
      (node (ref "Ce14") (pin "2") (pinfunction "2_2") (pintype "passive"))
      (node (ref "Ce15") (pin "2") (pinfunction "2_2") (pintype "passive"))
      (node (ref "Ce16") (pin "2") (pinfunction "2_2") (pintype "passive"))
      (node (ref "Ce17") (pin "2") (pinfunction "2_2") (pintype "passive"))
      (node (ref "Ce18") (pin "2") (pinfunction "2_2") (pintype "passive"))
      (node (ref "Ce19") (pin "2") (pinfunction "2_2") (pintype "passive"))
      (node (ref "Ce2") (pin "2") (pinfunction "2_2") (pintype "passive"))
      (node (ref "Ce20") (pin "2") (pinfunction "2_2") (pintype "passive"))
      (node (ref "Ce3") (pin "2") (pinfunction "2_2") (pintype "passive"))
      (node (ref "Ce4") (pin "2") (pinfunction "2_2") (pintype "passive"))
      (node (ref "Ce5") (pin "2") (pinfunction "2_2") (pintype "passive"))
      (node (ref "Ce6") (pin "2") (pinfunction "2_2") (pintype "passive"))
      (node (ref "Ce7") (pin "2") (pinfunction "2_2") (pintype "passive"))
      (node (ref "Ce8") (pin "2") (pinfunction "2_2") (pintype "passive"))
      (node (ref "Ce9") (pin "2") (pinfunction "2_2") (pintype "passive"))
      (node (ref "Re1") (pin "2") (pinfunction "2_2") (pintype "passive"))
      (node (ref "Re10") (pin "2") (pinfunction "2_2") (pintype "passive"))
      (node (ref "Re11") (pin "2") (pinfunction "2_2") (pintype "passive"))
      (node (ref "Re12") (pin "2") (pinfunction "2_2") (pintype "passive"))
      (node (ref "Re13") (pin "2") (pinfunction "2_2") (pintype "passive"))
      (node (ref "Re14") (pin "2") (pinfunction "2_2") (pintype "passive"))
      (node (ref "Re15") (pin "2") (pinfunction "2_2") (pintype "passive"))
      (node (ref "Re16") (pin "2") (pinfunction "2_2") (pintype "passive"))
      (node (ref "Re17") (pin "2") (pinfunction "2_2") (pintype "passive"))
      (node (ref "Re18") (pin "2") (pinfunction "2_2") (pintype "passive"))
      (node (ref "Re19") (pin "2") (pinfunction "2_2") (pintype "passive"))
      (node (ref "Re2") (pin "2") (pinfunction "2_2") (pintype "passive"))
      (node (ref "Re20") (pin "2") (pinfunction "2_2") (pintype "passive"))
      (node (ref "Re3") (pin "2") (pinfunction "2_2") (pintype "passive"))
      (node (ref "Re4") (pin "2") (pinfunction "2_2") (pintype "passive"))
      (node (ref "Re5") (pin "2") (pinfunction "2_2") (pintype "passive"))
      (node (ref "Re6") (pin "2") (pinfunction "2_2") (pintype "passive"))
      (node (ref "Re7") (pin "2") (pinfunction "2_2") (pintype "passive"))
      (node (ref "Re8") (pin "2") (pinfunction "2_2") (pintype "passive"))
      (node (ref "Re9") (pin "2") (pinfunction "2_2") (pintype "passive"))
      (node (ref "U1") (pin "8") (pinfunction "E/D_8") (pintype "input"))
      (node (ref "U10") (pin "8") (pinfunction "E/D_8") (pintype "input"))
      (node (ref "U11") (pin "8") (pinfunction "E/D_8") (pintype "input"))
      (node (ref "U12") (pin "8") (pinfunction "E/D_8") (pintype "input"))
      (node (ref "U13") (pin "8") (pinfunction "E/D_8") (pintype "input"))
      (node (ref "U14") (pin "8") (pinfunction "E/D_8") (pintype "input"))
      (node (ref "U15") (pin "8") (pinfunction "E/D_8") (pintype "input"))
      (node (ref "U16") (pin "8") (pinfunction "E/D_8") (pintype "input"))
      (node (ref "U17") (pin "8") (pinfunction "E/D_8") (pintype "input"))
      (node (ref "U18") (pin "8") (pinfunction "E/D_8") (pintype "input"))
      (node (ref "U19") (pin "8") (pinfunction "E/D_8") (pintype "input"))
      (node (ref "U2") (pin "8") (pinfunction "E/D_8") (pintype "input"))
      (node (ref "U20") (pin "8") (pinfunction "E/D_8") (pintype "input"))
      (node (ref "U3") (pin "8") (pinfunction "E/D_8") (pintype "input"))
      (node (ref "U4") (pin "8") (pinfunction "E/D_8") (pintype "input"))
      (node (ref "U5") (pin "8") (pinfunction "E/D_8") (pintype "input"))
      (node (ref "U6") (pin "8") (pinfunction "E/D_8") (pintype "input"))
      (node (ref "U7") (pin "8") (pinfunction "E/D_8") (pintype "input"))
      (node (ref "U8") (pin "8") (pinfunction "E/D_8") (pintype "input"))
      (node (ref "U9") (pin "8") (pinfunction "E/D_8") (pintype "input"))
    )
    (net (code "2") (name "+50V") (class "Default")
      (node (ref "Cd101") (pin "2") (pinfunction "2_2") (pintype "passive"))
      (node (ref "Cd102") (pin "1") (pinfunction "1_1") (pintype "passive"))
      (node (ref "Cd11") (pin "2") (pinfunction "2_2") (pintype "passive"))
      (node (ref "Cd111") (pin "2") (pinfunction "2_2") (pintype "passive"))
      (node (ref "Cd112") (pin "1") (pinfunction "1_1") (pintype "passive"))
      (node (ref "Cd12") (pin "1") (pinfunction "1_1") (pintype "passive"))
      (node (ref "Cd121") (pin "2") (pinfunction "2_2") (pintype "passive"))
      (node (ref "Cd122") (pin "1") (pinfunction "1_1") (pintype "passive"))
      (node (ref "Cd131") (pin "2") (pinfunction "2_2") (pintype "passive"))
      (node (ref "Cd132") (pin "1") (pinfunction "1_1") (pintype "passive"))
      (node (ref "Cd141") (pin "2") (pinfunction "2_2") (pintype "passive"))
      (node (ref "Cd142") (pin "1") (pinfunction "1_1") (pintype "passive"))
      (node (ref "Cd151") (pin "2") (pinfunction "2_2") (pintype "passive"))
      (node (ref "Cd152") (pin "1") (pinfunction "1_1") (pintype "passive"))
      (node (ref "Cd161") (pin "2") (pinfunction "2_2") (pintype "passive"))
      (node (ref "Cd162") (pin "1") (pinfunction "1_1") (pintype "passive"))
      (node (ref "Cd171") (pin "2") (pinfunction "2_2") (pintype "passive"))
      (node (ref "Cd172") (pin "1") (pinfunction "1_1") (pintype "passive"))
      (node (ref "Cd181") (pin "2") (pinfunction "2_2") (pintype "passive"))
      (node (ref "Cd182") (pin "1") (pinfunction "1_1") (pintype "passive"))
      (node (ref "Cd191") (pin "2") (pinfunction "2_2") (pintype "passive"))
      (node (ref "Cd192") (pin "1") (pinfunction "1_1") (pintype "passive"))
      (node (ref "Cd201") (pin "2") (pinfunction "2_2") (pintype "passive"))
      (node (ref "Cd202") (pin "1") (pinfunction "1_1") (pintype "passive"))
      (node (ref "Cd21") (pin "2") (pinfunction "2_2") (pintype "passive"))
      (node (ref "Cd22") (pin "1") (pinfunction "1_1") (pintype "passive"))
      (node (ref "Cd31") (pin "2") (pinfunction "2_2") (pintype "passive"))
      (node (ref "Cd32") (pin "1") (pinfunction "1_1") (pintype "passive"))
      (node (ref "Cd41") (pin "2") (pinfunction "2_2") (pintype "passive"))
      (node (ref "Cd42") (pin "1") (pinfunction "1_1") (pintype "passive"))
      (node (ref "Cd51") (pin "2") (pinfunction "2_2") (pintype "passive"))
      (node (ref "Cd52") (pin "1") (pinfunction "1_1") (pintype "passive"))
      (node (ref "Cd61") (pin "2") (pinfunction "2_2") (pintype "passive"))
      (node (ref "Cd62") (pin "1") (pinfunction "1_1") (pintype "passive"))
      (node (ref "Cd71") (pin "2") (pinfunction "2_2") (pintype "passive"))
      (node (ref "Cd72") (pin "1") (pinfunction "1_1") (pintype "passive"))
      (node (ref "Cd81") (pin "2") (pinfunction "2_2") (pintype "passive"))
      (node (ref "Cd82") (pin "1") (pinfunction "1_1") (pintype "passive"))
      (node (ref "Cd91") (pin "2") (pinfunction "2_2") (pintype "passive"))
      (node (ref "Cd92") (pin "1") (pinfunction "1_1") (pintype "passive"))
      (node (ref "Cout+") (pin "2") (pinfunction "2_2") (pintype "passive"))
      (node (ref "D1+") (pin "2") (pinfunction "A_2") (pintype "passive"))
      (node (ref "D2+") (pin "1") (pinfunction "K_1") (pintype "passive"))
      (node (ref "R1+") (pin "2") (pinfunction "2_2") (pintype "passive"))
      (node (ref "U+") (pin "2") (pinfunction "OUT_2") (pintype "power_in"))
      (node (ref "U1") (pin "7") (pinfunction "V+_7") (pintype "power_in"))
      (node (ref "U10") (pin "7") (pinfunction "V+_7") (pintype "power_in"))
      (node (ref "U11") (pin "7") (pinfunction "V+_7") (pintype "power_in"))
      (node (ref "U12") (pin "7") (pinfunction "V+_7") (pintype "power_in"))
      (node (ref "U13") (pin "7") (pinfunction "V+_7") (pintype "power_in"))
      (node (ref "U14") (pin "7") (pinfunction "V+_7") (pintype "power_in"))
      (node (ref "U15") (pin "7") (pinfunction "V+_7") (pintype "power_in"))
      (node (ref "U16") (pin "7") (pinfunction "V+_7") (pintype "power_in"))
      (node (ref "U17") (pin "7") (pinfunction "V+_7") (pintype "power_in"))
      (node (ref "U18") (pin "7") (pinfunction "V+_7") (pintype "power_in"))
      (node (ref "U19") (pin "7") (pinfunction "V+_7") (pintype "power_in"))
      (node (ref "U2") (pin "7") (pinfunction "V+_7") (pintype "power_in"))
      (node (ref "U20") (pin "7") (pinfunction "V+_7") (pintype "power_in"))
      (node (ref "U3") (pin "7") (pinfunction "V+_7") (pintype "power_in"))
      (node (ref "U4") (pin "7") (pinfunction "V+_7") (pintype "power_in"))
      (node (ref "U5") (pin "7") (pinfunction "V+_7") (pintype "power_in"))
      (node (ref "U6") (pin "7") (pinfunction "V+_7") (pintype "power_in"))
      (node (ref "U7") (pin "7") (pinfunction "V+_7") (pintype "power_in"))
      (node (ref "U8") (pin "7") (pinfunction "V+_7") (pintype "power_in"))
      (node (ref "U9") (pin "7") (pinfunction "V+_7") (pintype "power_in"))
    )
    (net (code "3") (name "+60V") (class "Default")
      (node (ref "Cin+") (pin "1") (pinfunction "1_1") (pintype "passive"))
      (node (ref "D1+") (pin "1") (pinfunction "K_1") (pintype "passive"))
      (node (ref "U+") (pin "3") (pinfunction "IN_3") (pintype "power_in"))
    )
    (net (code "4") (name "-50V") (class "Default")
      (node (ref "Cd103") (pin "2") (pinfunction "2_2") (pintype "passive"))
      (node (ref "Cd104") (pin "1") (pinfunction "1_1") (pintype "passive"))
      (node (ref "Cd113") (pin "2") (pinfunction "2_2") (pintype "passive"))
      (node (ref "Cd114") (pin "1") (pinfunction "1_1") (pintype "passive"))
      (node (ref "Cd123") (pin "2") (pinfunction "2_2") (pintype "passive"))
      (node (ref "Cd124") (pin "1") (pinfunction "1_1") (pintype "passive"))
      (node (ref "Cd13") (pin "2") (pinfunction "2_2") (pintype "passive"))
      (node (ref "Cd133") (pin "2") (pinfunction "2_2") (pintype "passive"))
      (node (ref "Cd134") (pin "1") (pinfunction "1_1") (pintype "passive"))
      (node (ref "Cd14") (pin "1") (pinfunction "1_1") (pintype "passive"))
      (node (ref "Cd143") (pin "2") (pinfunction "2_2") (pintype "passive"))
      (node (ref "Cd144") (pin "1") (pinfunction "1_1") (pintype "passive"))
      (node (ref "Cd153") (pin "2") (pinfunction "2_2") (pintype "passive"))
      (node (ref "Cd154") (pin "1") (pinfunction "1_1") (pintype "passive"))
      (node (ref "Cd163") (pin "2") (pinfunction "2_2") (pintype "passive"))
      (node (ref "Cd164") (pin "1") (pinfunction "1_1") (pintype "passive"))
      (node (ref "Cd173") (pin "2") (pinfunction "2_2") (pintype "passive"))
      (node (ref "Cd174") (pin "1") (pinfunction "1_1") (pintype "passive"))
      (node (ref "Cd183") (pin "2") (pinfunction "2_2") (pintype "passive"))
      (node (ref "Cd184") (pin "1") (pinfunction "1_1") (pintype "passive"))
      (node (ref "Cd193") (pin "2") (pinfunction "2_2") (pintype "passive"))
      (node (ref "Cd194") (pin "1") (pinfunction "1_1") (pintype "passive"))
      (node (ref "Cd203") (pin "2") (pinfunction "2_2") (pintype "passive"))
      (node (ref "Cd204") (pin "1") (pinfunction "1_1") (pintype "passive"))
      (node (ref "Cd23") (pin "2") (pinfunction "2_2") (pintype "passive"))
      (node (ref "Cd24") (pin "1") (pinfunction "1_1") (pintype "passive"))
      (node (ref "Cd33") (pin "2") (pinfunction "2_2") (pintype "passive"))
      (node (ref "Cd34") (pin "1") (pinfunction "1_1") (pintype "passive"))
      (node (ref "Cd43") (pin "2") (pinfunction "2_2") (pintype "passive"))
      (node (ref "Cd44") (pin "1") (pinfunction "1_1") (pintype "passive"))
      (node (ref "Cd53") (pin "2") (pinfunction "2_2") (pintype "passive"))
      (node (ref "Cd54") (pin "1") (pinfunction "1_1") (pintype "passive"))
      (node (ref "Cd63") (pin "2") (pinfunction "2_2") (pintype "passive"))
      (node (ref "Cd64") (pin "1") (pinfunction "1_1") (pintype "passive"))
      (node (ref "Cd73") (pin "2") (pinfunction "2_2") (pintype "passive"))
      (node (ref "Cd74") (pin "1") (pinfunction "1_1") (pintype "passive"))
      (node (ref "Cd83") (pin "2") (pinfunction "2_2") (pintype "passive"))
      (node (ref "Cd84") (pin "1") (pinfunction "1_1") (pintype "passive"))
      (node (ref "Cd93") (pin "2") (pinfunction "2_2") (pintype "passive"))
      (node (ref "Cd94") (pin "1") (pinfunction "1_1") (pintype "passive"))
      (node (ref "Cout-") (pin "2") (pinfunction "2_2") (pintype "passive"))
      (node (ref "D1-") (pin "1") (pinfunction "K_1") (pintype "passive"))
      (node (ref "D2-") (pin "2") (pinfunction "A_2") (pintype "passive"))
      (node (ref "R1-") (pin "2") (pinfunction "2_2") (pintype "passive"))
      (node (ref "U-") (pin "3") (pinfunction "OUT_3") (pintype "power_in"))
      (node (ref "U1") (pin "4") (pinfunction "V-_4") (pintype "power_in"))
      (node (ref "U1") (pin "9") (pinfunction "EP_9") (pintype "power_in"))
      (node (ref "U10") (pin "4") (pinfunction "V-_4") (pintype "power_in"))
      (node (ref "U10") (pin "9") (pinfunction "EP_9") (pintype "power_in"))
      (node (ref "U11") (pin "4") (pinfunction "V-_4") (pintype "power_in"))
      (node (ref "U11") (pin "9") (pinfunction "EP_9") (pintype "power_in"))
      (node (ref "U12") (pin "4") (pinfunction "V-_4") (pintype "power_in"))
      (node (ref "U12") (pin "9") (pinfunction "EP_9") (pintype "power_in"))
      (node (ref "U13") (pin "4") (pinfunction "V-_4") (pintype "power_in"))
      (node (ref "U13") (pin "9") (pinfunction "EP_9") (pintype "power_in"))
      (node (ref "U14") (pin "4") (pinfunction "V-_4") (pintype "power_in"))
      (node (ref "U14") (pin "9") (pinfunction "EP_9") (pintype "power_in"))
      (node (ref "U15") (pin "4") (pinfunction "V-_4") (pintype "power_in"))
      (node (ref "U15") (pin "9") (pinfunction "EP_9") (pintype "power_in"))
      (node (ref "U16") (pin "4") (pinfunction "V-_4") (pintype "power_in"))
      (node (ref "U16") (pin "9") (pinfunction "EP_9") (pintype "power_in"))
      (node (ref "U17") (pin "4") (pinfunction "V-_4") (pintype "power_in"))
      (node (ref "U17") (pin "9") (pinfunction "EP_9") (pintype "power_in"))
      (node (ref "U18") (pin "4") (pinfunction "V-_4") (pintype "power_in"))
      (node (ref "U18") (pin "9") (pinfunction "EP_9") (pintype "power_in"))
      (node (ref "U19") (pin "4") (pinfunction "V-_4") (pintype "power_in"))
      (node (ref "U19") (pin "9") (pinfunction "EP_9") (pintype "power_in"))
      (node (ref "U2") (pin "4") (pinfunction "V-_4") (pintype "power_in"))
      (node (ref "U2") (pin "9") (pinfunction "EP_9") (pintype "power_in"))
      (node (ref "U20") (pin "4") (pinfunction "V-_4") (pintype "power_in"))
      (node (ref "U20") (pin "9") (pinfunction "EP_9") (pintype "power_in"))
      (node (ref "U3") (pin "4") (pinfunction "V-_4") (pintype "power_in"))
      (node (ref "U3") (pin "9") (pinfunction "EP_9") (pintype "power_in"))
      (node (ref "U4") (pin "4") (pinfunction "V-_4") (pintype "power_in"))
      (node (ref "U4") (pin "9") (pinfunction "EP_9") (pintype "power_in"))
      (node (ref "U5") (pin "4") (pinfunction "V-_4") (pintype "power_in"))
      (node (ref "U5") (pin "9") (pinfunction "EP_9") (pintype "power_in"))
      (node (ref "U6") (pin "4") (pinfunction "V-_4") (pintype "power_in"))
      (node (ref "U6") (pin "9") (pinfunction "EP_9") (pintype "power_in"))
      (node (ref "U7") (pin "4") (pinfunction "V-_4") (pintype "power_in"))
      (node (ref "U7") (pin "9") (pinfunction "EP_9") (pintype "power_in"))
      (node (ref "U8") (pin "4") (pinfunction "V-_4") (pintype "power_in"))
      (node (ref "U8") (pin "9") (pinfunction "EP_9") (pintype "power_in"))
      (node (ref "U9") (pin "4") (pinfunction "V-_4") (pintype "power_in"))
      (node (ref "U9") (pin "9") (pinfunction "EP_9") (pintype "power_in"))
    )
    (net (code "5") (name "-60V") (class "Default")
      (node (ref "Cin-") (pin "1") (pinfunction "1_1") (pintype "passive"))
      (node (ref "D1-") (pin "2") (pinfunction "A_2") (pintype "passive"))
      (node (ref "U-") (pin "2") (pinfunction "IN_2") (pintype "power_in"))
    )
    (net (code "6") (name "CH1A") (class "Default")
      (node (ref "Rf1") (pin "2") (pinfunction "2_2") (pintype "passive"))
      (node (ref "T1") (pin "3") (pinfunction "DC_3") (pintype "input"))
      (node (ref "U1") (pin "6") (pinfunction "OUT_6") (pintype "output"))
    )
    (net (code "7") (name "CH1F") (class "Default")
      (node (ref "C1") (pin "2") (pinfunction "2_2") (pintype "passive"))
      (node (ref "R1") (pin "2") (pinfunction "2_2") (pintype "passive"))
      (node (ref "U1") (pin "3") (pinfunction "IN+_3") (pintype "input"))
    )
    (net (code "8") (name "CH1IN") (class "Default")
      (node (ref "JIN") (pin "1") (pinfunction "Z0_1") (pintype "passive"))
      (node (ref "R1") (pin "1") (pinfunction "1_1") (pintype "passive"))
    )
    (net (code "9") (name "CH1OUT") (class "Default")
      (node (ref "JOUT") (pin "1") (pinfunction "1_1") (pintype "passive"))
      (node (ref "T1") (pin "12") (pinfunction "DC+RF_12") (pintype "output"))
    )
    (net (code "10") (name "CH2A") (class "Default")
      (node (ref "JOUT") (pin "2") (pinfunction "2_2") (pintype "passive"))
      (node (ref "Rf2") (pin "2") (pinfunction "2_2") (pintype "passive"))
      (node (ref "U2") (pin "6") (pinfunction "OUT_6") (pintype "output"))
    )
    (net (code "11") (name "CH2F") (class "Default")
      (node (ref "C2") (pin "2") (pinfunction "2_2") (pintype "passive"))
      (node (ref "R2") (pin "2") (pinfunction "2_2") (pintype "passive"))
      (node (ref "U2") (pin "3") (pinfunction "IN+_3") (pintype "input"))
    )
    (net (code "12") (name "CH2IN") (class "Default")
      (node (ref "JIN") (pin "2") (pinfunction "Z1_2") (pintype "passive"))
      (node (ref "R2") (pin "1") (pinfunction "1_1") (pintype "passive"))
    )
    (net (code "13") (name "CH3A") (class "Default")
      (node (ref "Rf3") (pin "2") (pinfunction "2_2") (pintype "passive"))
      (node (ref "T3") (pin "3") (pinfunction "DC_3") (pintype "input"))
      (node (ref "U3") (pin "6") (pinfunction "OUT_6") (pintype "output"))
    )
    (net (code "14") (name "CH3F") (class "Default")
      (node (ref "C3") (pin "2") (pinfunction "2_2") (pintype "passive"))
      (node (ref "R3") (pin "2") (pinfunction "2_2") (pintype "passive"))
      (node (ref "U3") (pin "3") (pinfunction "IN+_3") (pintype "input"))
    )
    (net (code "15") (name "CH3IN") (class "Default")
      (node (ref "JIN") (pin "3") (pinfunction "Z2_3") (pintype "passive"))
      (node (ref "R3") (pin "1") (pinfunction "1_1") (pintype "passive"))
    )
    (net (code "16") (name "CH3OUT") (class "Default")
      (node (ref "JOUT") (pin "3") (pinfunction "3_3") (pintype "passive"))
      (node (ref "T3") (pin "12") (pinfunction "DC+RF_12") (pintype "output"))
    )
    (net (code "17") (name "CH4A") (class "Default")
      (node (ref "JOUT") (pin "4") (pinfunction "4_4") (pintype "passive"))
      (node (ref "Rf4") (pin "2") (pinfunction "2_2") (pintype "passive"))
      (node (ref "U4") (pin "6") (pinfunction "OUT_6") (pintype "output"))
    )
    (net (code "18") (name "CH4F") (class "Default")
      (node (ref "C4") (pin "2") (pinfunction "2_2") (pintype "passive"))
      (node (ref "R4") (pin "2") (pinfunction "2_2") (pintype "passive"))
      (node (ref "U4") (pin "3") (pinfunction "IN+_3") (pintype "input"))
    )
    (net (code "19") (name "CH4IN") (class "Default")
      (node (ref "JIN") (pin "4") (pinfunction "Z3_4") (pintype "passive"))
      (node (ref "R4") (pin "1") (pinfunction "1_1") (pintype "passive"))
    )
    (net (code "20") (name "CH5A") (class "Default")
      (node (ref "JOUT") (pin "5") (pinfunction "5_5") (pintype "passive"))
      (node (ref "Rf5") (pin "2") (pinfunction "2_2") (pintype "passive"))
      (node (ref "U5") (pin "6") (pinfunction "OUT_6") (pintype "output"))
    )
    (net (code "21") (name "CH5F") (class "Default")
      (node (ref "C5") (pin "2") (pinfunction "2_2") (pintype "passive"))
      (node (ref "R5") (pin "2") (pinfunction "2_2") (pintype "passive"))
      (node (ref "U5") (pin "3") (pinfunction "IN+_3") (pintype "input"))
    )
    (net (code "22") (name "CH5IN") (class "Default")
      (node (ref "JIN") (pin "5") (pinfunction "Z4_5") (pintype "passive"))
      (node (ref "R5") (pin "1") (pinfunction "1_1") (pintype "passive"))
    )
    (net (code "23") (name "CH6A") (class "Default")
      (node (ref "JOUT") (pin "9") (pinfunction "9_9") (pintype "passive"))
      (node (ref "Rf6") (pin "2") (pinfunction "2_2") (pintype "passive"))
      (node (ref "U6") (pin "6") (pinfunction "OUT_6") (pintype "output"))
    )
    (net (code "24") (name "CH6F") (class "Default")
      (node (ref "C6") (pin "2") (pinfunction "2_2") (pintype "passive"))
      (node (ref "R6") (pin "2") (pinfunction "2_2") (pintype "passive"))
      (node (ref "U6") (pin "3") (pinfunction "IN+_3") (pintype "input"))
    )
    (net (code "25") (name "CH6IN") (class "Default")
      (node (ref "JIN") (pin "6") (pinfunction "Z5_6") (pintype "passive"))
      (node (ref "R6") (pin "1") (pinfunction "1_1") (pintype "passive"))
    )
    (net (code "26") (name "CH7A") (class "Default")
      (node (ref "JOUT") (pin "10") (pinfunction "10_10") (pintype "passive"))
      (node (ref "Rf7") (pin "2") (pinfunction "2_2") (pintype "passive"))
      (node (ref "U7") (pin "6") (pinfunction "OUT_6") (pintype "output"))
    )
    (net (code "27") (name "CH7F") (class "Default")
      (node (ref "C7") (pin "2") (pinfunction "2_2") (pintype "passive"))
      (node (ref "R7") (pin "2") (pinfunction "2_2") (pintype "passive"))
      (node (ref "U7") (pin "3") (pinfunction "IN+_3") (pintype "input"))
    )
    (net (code "28") (name "CH7IN") (class "Default")
      (node (ref "JIN") (pin "7") (pinfunction "Z6_7") (pintype "passive"))
      (node (ref "R7") (pin "1") (pinfunction "1_1") (pintype "passive"))
    )
    (net (code "29") (name "CH8A") (class "Default")
      (node (ref "Rf8") (pin "2") (pinfunction "2_2") (pintype "passive"))
      (node (ref "T8") (pin "3") (pinfunction "DC_3") (pintype "input"))
      (node (ref "U8") (pin "6") (pinfunction "OUT_6") (pintype "output"))
    )
    (net (code "30") (name "CH8F") (class "Default")
      (node (ref "C8") (pin "2") (pinfunction "2_2") (pintype "passive"))
      (node (ref "R8") (pin "2") (pinfunction "2_2") (pintype "passive"))
      (node (ref "U8") (pin "3") (pinfunction "IN+_3") (pintype "input"))
    )
    (net (code "31") (name "CH8IN") (class "Default")
      (node (ref "JIN") (pin "8") (pinfunction "Z7_8") (pintype "passive"))
      (node (ref "R8") (pin "1") (pinfunction "1_1") (pintype "passive"))
    )
    (net (code "32") (name "CH8OUT") (class "Default")
      (node (ref "JOUT") (pin "11") (pinfunction "11_11") (pintype "passive"))
      (node (ref "T8") (pin "12") (pinfunction "DC+RF_12") (pintype "output"))
    )
    (net (code "33") (name "CH9A") (class "Default")
      (node (ref "JOUT") (pin "12") (pinfunction "12_12") (pintype "passive"))
      (node (ref "Rf9") (pin "2") (pinfunction "2_2") (pintype "passive"))
      (node (ref "U9") (pin "6") (pinfunction "OUT_6") (pintype "output"))
    )
    (net (code "34") (name "CH9F") (class "Default")
      (node (ref "C9") (pin "2") (pinfunction "2_2") (pintype "passive"))
      (node (ref "R9") (pin "2") (pinfunction "2_2") (pintype "passive"))
      (node (ref "U9") (pin "3") (pinfunction "IN+_3") (pintype "input"))
    )
    (net (code "35") (name "CH9IN") (class "Default")
      (node (ref "JIN") (pin "9") (pinfunction "Z8_9") (pintype "passive"))
      (node (ref "R9") (pin "1") (pinfunction "1_1") (pintype "passive"))
    )
    (net (code "36") (name "CH10A") (class "Default")
      (node (ref "Rf10") (pin "2") (pinfunction "2_2") (pintype "passive"))
      (node (ref "T10") (pin "3") (pinfunction "DC_3") (pintype "input"))
      (node (ref "U10") (pin "6") (pinfunction "OUT_6") (pintype "output"))
    )
    (net (code "37") (name "CH10F") (class "Default")
      (node (ref "C10") (pin "2") (pinfunction "2_2") (pintype "passive"))
      (node (ref "R10") (pin "2") (pinfunction "2_2") (pintype "passive"))
      (node (ref "U10") (pin "3") (pinfunction "IN+_3") (pintype "input"))
    )
    (net (code "38") (name "CH10IN") (class "Default")
      (node (ref "JIN") (pin "10") (pinfunction "Z9_10") (pintype "passive"))
      (node (ref "R10") (pin "1") (pinfunction "1_1") (pintype "passive"))
    )
    (net (code "39") (name "CH10OUT") (class "Default")
      (node (ref "JOUT") (pin "13") (pinfunction "13_13") (pintype "passive"))
      (node (ref "T10") (pin "12") (pinfunction "DC+RF_12") (pintype "output"))
    )
    (net (code "40") (name "CH11A") (class "Default")
      (node (ref "JOUT") (pin "14") (pinfunction "14_14") (pintype "passive"))
      (node (ref "Rf11") (pin "2") (pinfunction "2_2") (pintype "passive"))
      (node (ref "U11") (pin "6") (pinfunction "OUT_6") (pintype "output"))
    )
    (net (code "41") (name "CH11F") (class "Default")
      (node (ref "C11") (pin "2") (pinfunction "2_2") (pintype "passive"))
      (node (ref "R11") (pin "2") (pinfunction "2_2") (pintype "passive"))
      (node (ref "U11") (pin "3") (pinfunction "IN+_3") (pintype "input"))
    )
    (net (code "42") (name "CH11IN") (class "Default")
      (node (ref "JIN") (pin "11") (pinfunction "Z10_11") (pintype "passive"))
      (node (ref "R11") (pin "1") (pinfunction "1_1") (pintype "passive"))
    )
    (net (code "43") (name "CH12A") (class "Default")
      (node (ref "Rf12") (pin "2") (pinfunction "2_2") (pintype "passive"))
      (node (ref "T12") (pin "3") (pinfunction "DC_3") (pintype "input"))
      (node (ref "U12") (pin "6") (pinfunction "OUT_6") (pintype "output"))
    )
    (net (code "44") (name "CH12F") (class "Default")
      (node (ref "C12") (pin "2") (pinfunction "2_2") (pintype "passive"))
      (node (ref "R12") (pin "2") (pinfunction "2_2") (pintype "passive"))
      (node (ref "U12") (pin "3") (pinfunction "IN+_3") (pintype "input"))
    )
    (net (code "45") (name "CH12IN") (class "Default")
      (node (ref "JIN") (pin "12") (pinfunction "Z11_12") (pintype "passive"))
      (node (ref "R12") (pin "1") (pinfunction "1_1") (pintype "passive"))
    )
    (net (code "46") (name "CH12OUT") (class "Default")
      (node (ref "JOUT") (pin "15") (pinfunction "15_15") (pintype "passive"))
      (node (ref "T12") (pin "12") (pinfunction "DC+RF_12") (pintype "output"))
    )
    (net (code "47") (name "CH13A") (class "Default")
      (node (ref "JOUT") (pin "16") (pinfunction "16_16") (pintype "passive"))
      (node (ref "Rf13") (pin "2") (pinfunction "2_2") (pintype "passive"))
      (node (ref "U13") (pin "6") (pinfunction "OUT_6") (pintype "output"))
    )
    (net (code "48") (name "CH13F") (class "Default")
      (node (ref "C13") (pin "2") (pinfunction "2_2") (pintype "passive"))
      (node (ref "R13") (pin "2") (pinfunction "2_2") (pintype "passive"))
      (node (ref "U13") (pin "3") (pinfunction "IN+_3") (pintype "input"))
    )
    (net (code "49") (name "CH13IN") (class "Default")
      (node (ref "JIN") (pin "13") (pinfunction "Z12_13") (pintype "passive"))
      (node (ref "R13") (pin "1") (pinfunction "1_1") (pintype "passive"))
    )
    (net (code "50") (name "CH14A") (class "Default")
      (node (ref "JOUT") (pin "17") (pinfunction "17_17") (pintype "passive"))
      (node (ref "Rf14") (pin "2") (pinfunction "2_2") (pintype "passive"))
      (node (ref "U14") (pin "6") (pinfunction "OUT_6") (pintype "output"))
    )
    (net (code "51") (name "CH14F") (class "Default")
      (node (ref "C14") (pin "2") (pinfunction "2_2") (pintype "passive"))
      (node (ref "R14") (pin "2") (pinfunction "2_2") (pintype "passive"))
      (node (ref "U14") (pin "3") (pinfunction "IN+_3") (pintype "input"))
    )
    (net (code "52") (name "CH14IN") (class "Default")
      (node (ref "JIN") (pin "14") (pinfunction "Z13_14") (pintype "passive"))
      (node (ref "R14") (pin "1") (pinfunction "1_1") (pintype "passive"))
    )
    (net (code "53") (name "CH15A") (class "Default")
      (node (ref "JOUT") (pin "18") (pinfunction "18_18") (pintype "passive"))
      (node (ref "Rf15") (pin "2") (pinfunction "2_2") (pintype "passive"))
      (node (ref "U15") (pin "6") (pinfunction "OUT_6") (pintype "output"))
    )
    (net (code "54") (name "CH15F") (class "Default")
      (node (ref "C15") (pin "2") (pinfunction "2_2") (pintype "passive"))
      (node (ref "R15") (pin "2") (pinfunction "2_2") (pintype "passive"))
      (node (ref "U15") (pin "3") (pinfunction "IN+_3") (pintype "input"))
    )
    (net (code "55") (name "CH15IN") (class "Default")
      (node (ref "JIN") (pin "15") (pinfunction "Z14_15") (pintype "passive"))
      (node (ref "R15") (pin "1") (pinfunction "1_1") (pintype "passive"))
    )
    (net (code "56") (name "CH16A") (class "Default")
      (node (ref "JOUT") (pin "21") (pinfunction "21_21") (pintype "passive"))
      (node (ref "Rf16") (pin "2") (pinfunction "2_2") (pintype "passive"))
      (node (ref "U16") (pin "6") (pinfunction "OUT_6") (pintype "output"))
    )
    (net (code "57") (name "CH16F") (class "Default")
      (node (ref "C16") (pin "2") (pinfunction "2_2") (pintype "passive"))
      (node (ref "R16") (pin "2") (pinfunction "2_2") (pintype "passive"))
      (node (ref "U16") (pin "3") (pinfunction "IN+_3") (pintype "input"))
    )
    (net (code "58") (name "CH16IN") (class "Default")
      (node (ref "JIN") (pin "16") (pinfunction "Z15_16") (pintype "passive"))
      (node (ref "R16") (pin "1") (pinfunction "1_1") (pintype "passive"))
    )
    (net (code "59") (name "CH17A") (class "Default")
      (node (ref "JOUT") (pin "22") (pinfunction "22_22") (pintype "passive"))
      (node (ref "Rf17") (pin "2") (pinfunction "2_2") (pintype "passive"))
      (node (ref "U17") (pin "6") (pinfunction "OUT_6") (pintype "output"))
    )
    (net (code "60") (name "CH17F") (class "Default")
      (node (ref "C17") (pin "2") (pinfunction "2_2") (pintype "passive"))
      (node (ref "R17") (pin "2") (pinfunction "2_2") (pintype "passive"))
      (node (ref "U17") (pin "3") (pinfunction "IN+_3") (pintype "input"))
    )
    (net (code "61") (name "CH17IN") (class "Default")
      (node (ref "JIN") (pin "19") (pinfunction "Z16_19") (pintype "passive"))
      (node (ref "R17") (pin "1") (pinfunction "1_1") (pintype "passive"))
    )
    (net (code "62") (name "CH18A") (class "Default")
      (node (ref "JOUT") (pin "23") (pinfunction "23_23") (pintype "passive"))
      (node (ref "Rf18") (pin "2") (pinfunction "2_2") (pintype "passive"))
      (node (ref "U18") (pin "6") (pinfunction "OUT_6") (pintype "output"))
    )
    (net (code "63") (name "CH18F") (class "Default")
      (node (ref "C18") (pin "2") (pinfunction "2_2") (pintype "passive"))
      (node (ref "R18") (pin "2") (pinfunction "2_2") (pintype "passive"))
      (node (ref "U18") (pin "3") (pinfunction "IN+_3") (pintype "input"))
    )
    (net (code "64") (name "CH18IN") (class "Default")
      (node (ref "JIN") (pin "20") (pinfunction "Z17_20") (pintype "passive"))
      (node (ref "R18") (pin "1") (pinfunction "1_1") (pintype "passive"))
    )
    (net (code "65") (name "CH19A") (class "Default")
      (node (ref "Rf19") (pin "2") (pinfunction "2_2") (pintype "passive"))
      (node (ref "T19") (pin "3") (pinfunction "DC_3") (pintype "input"))
      (node (ref "U19") (pin "6") (pinfunction "OUT_6") (pintype "output"))
    )
    (net (code "66") (name "CH19F") (class "Default")
      (node (ref "C19") (pin "2") (pinfunction "2_2") (pintype "passive"))
      (node (ref "R19") (pin "2") (pinfunction "2_2") (pintype "passive"))
      (node (ref "U19") (pin "3") (pinfunction "IN+_3") (pintype "input"))
    )
    (net (code "67") (name "CH19IN") (class "Default")
      (node (ref "JIN") (pin "21") (pinfunction "Z18_21") (pintype "passive"))
      (node (ref "R19") (pin "1") (pinfunction "1_1") (pintype "passive"))
    )
    (net (code "68") (name "CH19OUT") (class "Default")
      (node (ref "JOUT") (pin "24") (pinfunction "24_24") (pintype "passive"))
      (node (ref "T19") (pin "12") (pinfunction "DC+RF_12") (pintype "output"))
    )
    (net (code "69") (name "CH20A") (class "Default")
      (node (ref "JOUT") (pin "25") (pinfunction "25_25") (pintype "passive"))
      (node (ref "Rf20") (pin "2") (pinfunction "2_2") (pintype "passive"))
      (node (ref "U20") (pin "6") (pinfunction "OUT_6") (pintype "output"))
    )
    (net (code "70") (name "CH20F") (class "Default")
      (node (ref "C20") (pin "2") (pinfunction "2_2") (pintype "passive"))
      (node (ref "R20") (pin "2") (pinfunction "2_2") (pintype "passive"))
      (node (ref "U20") (pin "3") (pinfunction "IN+_3") (pintype "input"))
    )
    (net (code "71") (name "CH20IN") (class "Default")
      (node (ref "JIN") (pin "22") (pinfunction "Z19_22") (pintype "passive"))
      (node (ref "R20") (pin "1") (pinfunction "1_1") (pintype "passive"))
    )
    (net (code "72") (name "GND") (class "Default")
      (node (ref "C1") (pin "1") (pinfunction "1_1") (pintype "passive"))
      (node (ref "C10") (pin "1") (pinfunction "1_1") (pintype "passive"))
      (node (ref "C11") (pin "1") (pinfunction "1_1") (pintype "passive"))
      (node (ref "C12") (pin "1") (pinfunction "1_1") (pintype "passive"))
      (node (ref "C13") (pin "1") (pinfunction "1_1") (pintype "passive"))
      (node (ref "C14") (pin "1") (pinfunction "1_1") (pintype "passive"))
      (node (ref "C15") (pin "1") (pinfunction "1_1") (pintype "passive"))
      (node (ref "C16") (pin "1") (pinfunction "1_1") (pintype "passive"))
      (node (ref "C17") (pin "1") (pinfunction "1_1") (pintype "passive"))
      (node (ref "C18") (pin "1") (pinfunction "1_1") (pintype "passive"))
      (node (ref "C19") (pin "1") (pinfunction "1_1") (pintype "passive"))
      (node (ref "C2") (pin "1") (pinfunction "1_1") (pintype "passive"))
      (node (ref "C20") (pin "1") (pinfunction "1_1") (pintype "passive"))
      (node (ref "C3") (pin "1") (pinfunction "1_1") (pintype "passive"))
      (node (ref "C4") (pin "1") (pinfunction "1_1") (pintype "passive"))
      (node (ref "C5") (pin "1") (pinfunction "1_1") (pintype "passive"))
      (node (ref "C6") (pin "1") (pinfunction "1_1") (pintype "passive"))
      (node (ref "C7") (pin "1") (pinfunction "1_1") (pintype "passive"))
      (node (ref "C8") (pin "1") (pinfunction "1_1") (pintype "passive"))
      (node (ref "C9") (pin "1") (pinfunction "1_1") (pintype "passive"))
      (node (ref "Cadj+") (pin "2") (pinfunction "2_2") (pintype "passive"))
      (node (ref "Cadj-") (pin "2") (pinfunction "2_2") (pintype "passive"))
      (node (ref "Cd101") (pin "1") (pinfunction "1_1") (pintype "passive"))
      (node (ref "Cd102") (pin "2") (pinfunction "2_2") (pintype "passive"))
      (node (ref "Cd103") (pin "1") (pinfunction "1_1") (pintype "passive"))
      (node (ref "Cd104") (pin "2") (pinfunction "2_2") (pintype "passive"))
      (node (ref "Cd11") (pin "1") (pinfunction "1_1") (pintype "passive"))
      (node (ref "Cd111") (pin "1") (pinfunction "1_1") (pintype "passive"))
      (node (ref "Cd112") (pin "2") (pinfunction "2_2") (pintype "passive"))
      (node (ref "Cd113") (pin "1") (pinfunction "1_1") (pintype "passive"))
      (node (ref "Cd114") (pin "2") (pinfunction "2_2") (pintype "passive"))
      (node (ref "Cd12") (pin "2") (pinfunction "2_2") (pintype "passive"))
      (node (ref "Cd121") (pin "1") (pinfunction "1_1") (pintype "passive"))
      (node (ref "Cd122") (pin "2") (pinfunction "2_2") (pintype "passive"))
      (node (ref "Cd123") (pin "1") (pinfunction "1_1") (pintype "passive"))
      (node (ref "Cd124") (pin "2") (pinfunction "2_2") (pintype "passive"))
      (node (ref "Cd13") (pin "1") (pinfunction "1_1") (pintype "passive"))
      (node (ref "Cd131") (pin "1") (pinfunction "1_1") (pintype "passive"))
      (node (ref "Cd132") (pin "2") (pinfunction "2_2") (pintype "passive"))
      (node (ref "Cd133") (pin "1") (pinfunction "1_1") (pintype "passive"))
      (node (ref "Cd134") (pin "2") (pinfunction "2_2") (pintype "passive"))
      (node (ref "Cd14") (pin "2") (pinfunction "2_2") (pintype "passive"))
      (node (ref "Cd141") (pin "1") (pinfunction "1_1") (pintype "passive"))
      (node (ref "Cd142") (pin "2") (pinfunction "2_2") (pintype "passive"))
      (node (ref "Cd143") (pin "1") (pinfunction "1_1") (pintype "passive"))
      (node (ref "Cd144") (pin "2") (pinfunction "2_2") (pintype "passive"))
      (node (ref "Cd151") (pin "1") (pinfunction "1_1") (pintype "passive"))
      (node (ref "Cd152") (pin "2") (pinfunction "2_2") (pintype "passive"))
      (node (ref "Cd153") (pin "1") (pinfunction "1_1") (pintype "passive"))
      (node (ref "Cd154") (pin "2") (pinfunction "2_2") (pintype "passive"))
      (node (ref "Cd161") (pin "1") (pinfunction "1_1") (pintype "passive"))
      (node (ref "Cd162") (pin "2") (pinfunction "2_2") (pintype "passive"))
      (node (ref "Cd163") (pin "1") (pinfunction "1_1") (pintype "passive"))
      (node (ref "Cd164") (pin "2") (pinfunction "2_2") (pintype "passive"))
      (node (ref "Cd171") (pin "1") (pinfunction "1_1") (pintype "passive"))
      (node (ref "Cd172") (pin "2") (pinfunction "2_2") (pintype "passive"))
      (node (ref "Cd173") (pin "1") (pinfunction "1_1") (pintype "passive"))
      (node (ref "Cd174") (pin "2") (pinfunction "2_2") (pintype "passive"))
      (node (ref "Cd181") (pin "1") (pinfunction "1_1") (pintype "passive"))
      (node (ref "Cd182") (pin "2") (pinfunction "2_2") (pintype "passive"))
      (node (ref "Cd183") (pin "1") (pinfunction "1_1") (pintype "passive"))
      (node (ref "Cd184") (pin "2") (pinfunction "2_2") (pintype "passive"))
      (node (ref "Cd191") (pin "1") (pinfunction "1_1") (pintype "passive"))
      (node (ref "Cd192") (pin "2") (pinfunction "2_2") (pintype "passive"))
      (node (ref "Cd193") (pin "1") (pinfunction "1_1") (pintype "passive"))
      (node (ref "Cd194") (pin "2") (pinfunction "2_2") (pintype "passive"))
      (node (ref "Cd201") (pin "1") (pinfunction "1_1") (pintype "passive"))
      (node (ref "Cd202") (pin "2") (pinfunction "2_2") (pintype "passive"))
      (node (ref "Cd203") (pin "1") (pinfunction "1_1") (pintype "passive"))
      (node (ref "Cd204") (pin "2") (pinfunction "2_2") (pintype "passive"))
      (node (ref "Cd21") (pin "1") (pinfunction "1_1") (pintype "passive"))
      (node (ref "Cd22") (pin "2") (pinfunction "2_2") (pintype "passive"))
      (node (ref "Cd23") (pin "1") (pinfunction "1_1") (pintype "passive"))
      (node (ref "Cd24") (pin "2") (pinfunction "2_2") (pintype "passive"))
      (node (ref "Cd31") (pin "1") (pinfunction "1_1") (pintype "passive"))
      (node (ref "Cd32") (pin "2") (pinfunction "2_2") (pintype "passive"))
      (node (ref "Cd33") (pin "1") (pinfunction "1_1") (pintype "passive"))
      (node (ref "Cd34") (pin "2") (pinfunction "2_2") (pintype "passive"))
      (node (ref "Cd41") (pin "1") (pinfunction "1_1") (pintype "passive"))
      (node (ref "Cd42") (pin "2") (pinfunction "2_2") (pintype "passive"))
      (node (ref "Cd43") (pin "1") (pinfunction "1_1") (pintype "passive"))
      (node (ref "Cd44") (pin "2") (pinfunction "2_2") (pintype "passive"))
      (node (ref "Cd51") (pin "1") (pinfunction "1_1") (pintype "passive"))
      (node (ref "Cd52") (pin "2") (pinfunction "2_2") (pintype "passive"))
      (node (ref "Cd53") (pin "1") (pinfunction "1_1") (pintype "passive"))
      (node (ref "Cd54") (pin "2") (pinfunction "2_2") (pintype "passive"))
      (node (ref "Cd61") (pin "1") (pinfunction "1_1") (pintype "passive"))
      (node (ref "Cd62") (pin "2") (pinfunction "2_2") (pintype "passive"))
      (node (ref "Cd63") (pin "1") (pinfunction "1_1") (pintype "passive"))
      (node (ref "Cd64") (pin "2") (pinfunction "2_2") (pintype "passive"))
      (node (ref "Cd71") (pin "1") (pinfunction "1_1") (pintype "passive"))
      (node (ref "Cd72") (pin "2") (pinfunction "2_2") (pintype "passive"))
      (node (ref "Cd73") (pin "1") (pinfunction "1_1") (pintype "passive"))
      (node (ref "Cd74") (pin "2") (pinfunction "2_2") (pintype "passive"))
      (node (ref "Cd81") (pin "1") (pinfunction "1_1") (pintype "passive"))
      (node (ref "Cd82") (pin "2") (pinfunction "2_2") (pintype "passive"))
      (node (ref "Cd83") (pin "1") (pinfunction "1_1") (pintype "passive"))
      (node (ref "Cd84") (pin "2") (pinfunction "2_2") (pintype "passive"))
      (node (ref "Cd91") (pin "1") (pinfunction "1_1") (pintype "passive"))
      (node (ref "Cd92") (pin "2") (pinfunction "2_2") (pintype "passive"))
      (node (ref "Cd93") (pin "1") (pinfunction "1_1") (pintype "passive"))
      (node (ref "Cd94") (pin "2") (pinfunction "2_2") (pintype "passive"))
      (node (ref "Ce1") (pin "1") (pinfunction "1_1") (pintype "passive"))
      (node (ref "Ce10") (pin "1") (pinfunction "1_1") (pintype "passive"))
      (node (ref "Ce11") (pin "1") (pinfunction "1_1") (pintype "passive"))
      (node (ref "Ce12") (pin "1") (pinfunction "1_1") (pintype "passive"))
      (node (ref "Ce13") (pin "1") (pinfunction "1_1") (pintype "passive"))
      (node (ref "Ce14") (pin "1") (pinfunction "1_1") (pintype "passive"))
      (node (ref "Ce15") (pin "1") (pinfunction "1_1") (pintype "passive"))
      (node (ref "Ce16") (pin "1") (pinfunction "1_1") (pintype "passive"))
      (node (ref "Ce17") (pin "1") (pinfunction "1_1") (pintype "passive"))
      (node (ref "Ce18") (pin "1") (pinfunction "1_1") (pintype "passive"))
      (node (ref "Ce19") (pin "1") (pinfunction "1_1") (pintype "passive"))
      (node (ref "Ce2") (pin "1") (pinfunction "1_1") (pintype "passive"))
      (node (ref "Ce20") (pin "1") (pinfunction "1_1") (pintype "passive"))
      (node (ref "Ce3") (pin "1") (pinfunction "1_1") (pintype "passive"))
      (node (ref "Ce4") (pin "1") (pinfunction "1_1") (pintype "passive"))
      (node (ref "Ce5") (pin "1") (pinfunction "1_1") (pintype "passive"))
      (node (ref "Ce6") (pin "1") (pinfunction "1_1") (pintype "passive"))
      (node (ref "Ce7") (pin "1") (pinfunction "1_1") (pintype "passive"))
      (node (ref "Ce8") (pin "1") (pinfunction "1_1") (pintype "passive"))
      (node (ref "Ce9") (pin "1") (pinfunction "1_1") (pintype "passive"))
      (node (ref "Cin+") (pin "2") (pinfunction "2_2") (pintype "passive"))
      (node (ref "Cin-") (pin "2") (pinfunction "2_2") (pintype "passive"))
      (node (ref "Cout+") (pin "1") (pinfunction "1_1") (pintype "passive"))
      (node (ref "Cout-") (pin "1") (pinfunction "1_1") (pintype "passive"))
      (node (ref "J1") (pin "2") (pinfunction "GND_2") (pintype "passive"))
      (node (ref "J1") (pin "3") (pinfunction "GND_3") (pintype "passive"))
      (node (ref "J1") (pin "4") (pinfunction "GND_4") (pintype "passive"))
      (node (ref "J1") (pin "5") (pinfunction "GND_5") (pintype "passive"))
      (node (ref "J10") (pin "2") (pinfunction "GND_2") (pintype "passive"))
      (node (ref "J10") (pin "3") (pinfunction "GND_3") (pintype "passive"))
      (node (ref "J10") (pin "4") (pinfunction "GND_4") (pintype "passive"))
      (node (ref "J10") (pin "5") (pinfunction "GND_5") (pintype "passive"))
      (node (ref "J12") (pin "2") (pinfunction "GND_2") (pintype "passive"))
      (node (ref "J12") (pin "3") (pinfunction "GND_3") (pintype "passive"))
      (node (ref "J12") (pin "4") (pinfunction "GND_4") (pintype "passive"))
      (node (ref "J12") (pin "5") (pinfunction "GND_5") (pintype "passive"))
      (node (ref "J19") (pin "2") (pinfunction "GND_2") (pintype "passive"))
      (node (ref "J19") (pin "3") (pinfunction "GND_3") (pintype "passive"))
      (node (ref "J19") (pin "4") (pinfunction "GND_4") (pintype "passive"))
      (node (ref "J19") (pin "5") (pinfunction "GND_5") (pintype "passive"))
      (node (ref "J3") (pin "2") (pinfunction "GND_2") (pintype "passive"))
      (node (ref "J3") (pin "3") (pinfunction "GND_3") (pintype "passive"))
      (node (ref "J3") (pin "4") (pinfunction "GND_4") (pintype "passive"))
      (node (ref "J3") (pin "5") (pinfunction "GND_5") (pintype "passive"))
      (node (ref "J8") (pin "2") (pinfunction "GND_2") (pintype "passive"))
      (node (ref "J8") (pin "3") (pinfunction "GND_3") (pintype "passive"))
      (node (ref "J8") (pin "4") (pinfunction "GND_4") (pintype "passive"))
      (node (ref "J8") (pin "5") (pinfunction "GND_5") (pintype "passive"))
      (node (ref "JIN") (pin "17") (pinfunction "GND1_17") (pintype "passive"))
      (node (ref "JIN") (pin "18") (pinfunction "GND2_18") (pintype "passive"))
      (node (ref "JIN") (pin "35") (pinfunction "35_35") (pintype "passive"))
      (node (ref "JIN") (pin "36") (pinfunction "36_36") (pintype "passive"))
      (node (ref "JIN") (pin "37") (pinfunction "37_37") (pintype "passive"))
      (node (ref "JIN") (pin "38") (pinfunction "38_38") (pintype "passive"))
      (node (ref "JIN") (pin "39") (pinfunction "39_39") (pintype "passive"))
      (node (ref "JIN") (pin "40") (pinfunction "40_40") (pintype "passive"))
      (node (ref "JIN") (pin "41") (pinfunction "41_41") (pintype "passive"))
      (node (ref "JIN") (pin "42") (pinfunction "42_42") (pintype "passive"))
      (node (ref "JIN") (pin "43") (pinfunction "43_43") (pintype "passive"))
      (node (ref "JIN") (pin "44") (pinfunction "44_44") (pintype "passive"))
      (node (ref "JIN") (pin "45") (pinfunction "45_45") (pintype "passive"))
      (node (ref "JIN") (pin "46") (pinfunction "46_46") (pintype "passive"))
      (node (ref "JIN") (pin "47") (pinfunction "47_47") (pintype "passive"))
      (node (ref "JIN") (pin "48") (pinfunction "48_48") (pintype "passive"))
      (node (ref "JIN") (pin "49") (pinfunction "49_49") (pintype "passive"))
      (node (ref "JIN") (pin "50") (pinfunction "50_50") (pintype "passive"))
      (node (ref "JIN") (pin "51") (pinfunction "51_51") (pintype "passive"))
      (node (ref "JIN") (pin "52") (pinfunction "52_52") (pintype "passive"))
      (node (ref "JIN") (pin "53") (pinfunction "53_53") (pintype "passive"))
      (node (ref "JIN") (pin "54") (pinfunction "54_54") (pintype "passive"))
      (node (ref "JIN") (pin "55") (pinfunction "55_55") (pintype "passive"))
      (node (ref "JIN") (pin "56") (pinfunction "56_56") (pintype "passive"))
      (node (ref "JIN") (pin "57") (pinfunction "57_57") (pintype "passive"))
      (node (ref "JIN") (pin "58") (pinfunction "58_58") (pintype "passive"))
      (node (ref "JIN") (pin "59") (pinfunction "59_59") (pintype "passive"))
      (node (ref "JIN") (pin "60") (pinfunction "60_60") (pintype "passive"))
      (node (ref "JIN") (pin "61") (pinfunction "61_61") (pintype "passive"))
      (node (ref "JIN") (pin "62") (pinfunction "62_62") (pintype "passive"))
      (node (ref "JIN") (pin "63") (pinfunction "63_63") (pintype "passive"))
      (node (ref "JIN") (pin "64") (pinfunction "64_64") (pintype "passive"))
      (node (ref "JIN") (pin "65") (pinfunction "65_65") (pintype "passive"))
      (node (ref "JIN") (pin "66") (pinfunction "66_66") (pintype "passive"))
      (node (ref "JIN") (pin "67") (pinfunction "67_67") (pintype "passive"))
      (node (ref "JIN") (pin "68") (pinfunction "68_68") (pintype "passive"))
      (node (ref "JIN") (pin "M1") (pinfunction "M1_M1") (pintype "passive"))
      (node (ref "JIN") (pin "M2") (pinfunction "M2_M2") (pintype "passive"))
      (node (ref "JOUT") (pin "19") (pinfunction "19_19") (pintype "passive"))
      (node (ref "JOUT") (pin "20") (pinfunction "20_20") (pintype "passive"))
      (node (ref "JOUT") (pin "6") (pinfunction "6_6") (pintype "passive"))
      (node (ref "JOUT") (pin "7") (pinfunction "7_7") (pintype "passive"))
      (node (ref "JOUT") (pin "8") (pinfunction "8_8") (pintype "passive"))
      (node (ref "JOUT") (pin "M1") (pinfunction "M1_M1") (pintype "passive"))
      (node (ref "JOUT") (pin "M2") (pinfunction "M2_M2") (pintype "passive"))
      (node (ref "R3+") (pin "2") (pinfunction "2_2") (pintype "passive"))
      (node (ref "R3-") (pin "1") (pinfunction "1_1") (pintype "passive"))
      (node (ref "Rg1") (pin "1") (pinfunction "1_1") (pintype "passive"))
      (node (ref "Rg10") (pin "1") (pinfunction "1_1") (pintype "passive"))
      (node (ref "Rg11") (pin "1") (pinfunction "1_1") (pintype "passive"))
      (node (ref "Rg12") (pin "1") (pinfunction "1_1") (pintype "passive"))
      (node (ref "Rg13") (pin "1") (pinfunction "1_1") (pintype "passive"))
      (node (ref "Rg14") (pin "1") (pinfunction "1_1") (pintype "passive"))
      (node (ref "Rg15") (pin "1") (pinfunction "1_1") (pintype "passive"))
      (node (ref "Rg16") (pin "1") (pinfunction "1_1") (pintype "passive"))
      (node (ref "Rg17") (pin "1") (pinfunction "1_1") (pintype "passive"))
      (node (ref "Rg18") (pin "1") (pinfunction "1_1") (pintype "passive"))
      (node (ref "Rg19") (pin "1") (pinfunction "1_1") (pintype "passive"))
      (node (ref "Rg2") (pin "1") (pinfunction "1_1") (pintype "passive"))
      (node (ref "Rg20") (pin "1") (pinfunction "1_1") (pintype "passive"))
      (node (ref "Rg3") (pin "1") (pinfunction "1_1") (pintype "passive"))
      (node (ref "Rg4") (pin "1") (pinfunction "1_1") (pintype "passive"))
      (node (ref "Rg5") (pin "1") (pinfunction "1_1") (pintype "passive"))
      (node (ref "Rg6") (pin "1") (pinfunction "1_1") (pintype "passive"))
      (node (ref "Rg7") (pin "1") (pinfunction "1_1") (pintype "passive"))
      (node (ref "Rg8") (pin "1") (pinfunction "1_1") (pintype "passive"))
      (node (ref "Rg9") (pin "1") (pinfunction "1_1") (pintype "passive"))
      (node (ref "T1") (pin "1") (pinfunction "1_1") (pintype "passive"))
      (node (ref "T1") (pin "10") (pinfunction "10_10") (pintype "passive"))
      (node (ref "T1") (pin "11") (pinfunction "11_11") (pintype "passive"))
      (node (ref "T1") (pin "13") (pinfunction "13_13") (pintype "passive"))
      (node (ref "T1") (pin "14") (pinfunction "14_14") (pintype "passive"))
      (node (ref "T1") (pin "15") (pinfunction "15_15") (pintype "passive"))
      (node (ref "T1") (pin "16") (pinfunction "16_16") (pintype "passive"))
      (node (ref "T1") (pin "2") (pinfunction "2_2") (pintype "passive"))
      (node (ref "T1") (pin "4") (pinfunction "4_4") (pintype "passive"))
      (node (ref "T1") (pin "5") (pinfunction "5_5") (pintype "passive"))
      (node (ref "T1") (pin "6") (pinfunction "6_6") (pintype "passive"))
      (node (ref "T1") (pin "7") (pinfunction "7_7") (pintype "passive"))
      (node (ref "T1") (pin "8") (pinfunction "8_8") (pintype "passive"))
      (node (ref "T10") (pin "1") (pinfunction "1_1") (pintype "passive"))
      (node (ref "T10") (pin "10") (pinfunction "10_10") (pintype "passive"))
      (node (ref "T10") (pin "11") (pinfunction "11_11") (pintype "passive"))
      (node (ref "T10") (pin "13") (pinfunction "13_13") (pintype "passive"))
      (node (ref "T10") (pin "14") (pinfunction "14_14") (pintype "passive"))
      (node (ref "T10") (pin "15") (pinfunction "15_15") (pintype "passive"))
      (node (ref "T10") (pin "16") (pinfunction "16_16") (pintype "passive"))
      (node (ref "T10") (pin "2") (pinfunction "2_2") (pintype "passive"))
      (node (ref "T10") (pin "4") (pinfunction "4_4") (pintype "passive"))
      (node (ref "T10") (pin "5") (pinfunction "5_5") (pintype "passive"))
      (node (ref "T10") (pin "6") (pinfunction "6_6") (pintype "passive"))
      (node (ref "T10") (pin "7") (pinfunction "7_7") (pintype "passive"))
      (node (ref "T10") (pin "8") (pinfunction "8_8") (pintype "passive"))
      (node (ref "T12") (pin "1") (pinfunction "1_1") (pintype "passive"))
      (node (ref "T12") (pin "10") (pinfunction "10_10") (pintype "passive"))
      (node (ref "T12") (pin "11") (pinfunction "11_11") (pintype "passive"))
      (node (ref "T12") (pin "13") (pinfunction "13_13") (pintype "passive"))
      (node (ref "T12") (pin "14") (pinfunction "14_14") (pintype "passive"))
      (node (ref "T12") (pin "15") (pinfunction "15_15") (pintype "passive"))
      (node (ref "T12") (pin "16") (pinfunction "16_16") (pintype "passive"))
      (node (ref "T12") (pin "2") (pinfunction "2_2") (pintype "passive"))
      (node (ref "T12") (pin "4") (pinfunction "4_4") (pintype "passive"))
      (node (ref "T12") (pin "5") (pinfunction "5_5") (pintype "passive"))
      (node (ref "T12") (pin "6") (pinfunction "6_6") (pintype "passive"))
      (node (ref "T12") (pin "7") (pinfunction "7_7") (pintype "passive"))
      (node (ref "T12") (pin "8") (pinfunction "8_8") (pintype "passive"))
      (node (ref "T19") (pin "1") (pinfunction "1_1") (pintype "passive"))
      (node (ref "T19") (pin "10") (pinfunction "10_10") (pintype "passive"))
      (node (ref "T19") (pin "11") (pinfunction "11_11") (pintype "passive"))
      (node (ref "T19") (pin "13") (pinfunction "13_13") (pintype "passive"))
      (node (ref "T19") (pin "14") (pinfunction "14_14") (pintype "passive"))
      (node (ref "T19") (pin "15") (pinfunction "15_15") (pintype "passive"))
      (node (ref "T19") (pin "16") (pinfunction "16_16") (pintype "passive"))
      (node (ref "T19") (pin "2") (pinfunction "2_2") (pintype "passive"))
      (node (ref "T19") (pin "4") (pinfunction "4_4") (pintype "passive"))
      (node (ref "T19") (pin "5") (pinfunction "5_5") (pintype "passive"))
      (node (ref "T19") (pin "6") (pinfunction "6_6") (pintype "passive"))
      (node (ref "T19") (pin "7") (pinfunction "7_7") (pintype "passive"))
      (node (ref "T19") (pin "8") (pinfunction "8_8") (pintype "passive"))
      (node (ref "T3") (pin "1") (pinfunction "1_1") (pintype "passive"))
      (node (ref "T3") (pin "10") (pinfunction "10_10") (pintype "passive"))
      (node (ref "T3") (pin "11") (pinfunction "11_11") (pintype "passive"))
      (node (ref "T3") (pin "13") (pinfunction "13_13") (pintype "passive"))
      (node (ref "T3") (pin "14") (pinfunction "14_14") (pintype "passive"))
      (node (ref "T3") (pin "15") (pinfunction "15_15") (pintype "passive"))
      (node (ref "T3") (pin "16") (pinfunction "16_16") (pintype "passive"))
      (node (ref "T3") (pin "2") (pinfunction "2_2") (pintype "passive"))
      (node (ref "T3") (pin "4") (pinfunction "4_4") (pintype "passive"))
      (node (ref "T3") (pin "5") (pinfunction "5_5") (pintype "passive"))
      (node (ref "T3") (pin "6") (pinfunction "6_6") (pintype "passive"))
      (node (ref "T3") (pin "7") (pinfunction "7_7") (pintype "passive"))
      (node (ref "T3") (pin "8") (pinfunction "8_8") (pintype "passive"))
      (node (ref "T8") (pin "1") (pinfunction "1_1") (pintype "passive"))
      (node (ref "T8") (pin "10") (pinfunction "10_10") (pintype "passive"))
      (node (ref "T8") (pin "11") (pinfunction "11_11") (pintype "passive"))
      (node (ref "T8") (pin "13") (pinfunction "13_13") (pintype "passive"))
      (node (ref "T8") (pin "14") (pinfunction "14_14") (pintype "passive"))
      (node (ref "T8") (pin "15") (pinfunction "15_15") (pintype "passive"))
      (node (ref "T8") (pin "16") (pinfunction "16_16") (pintype "passive"))
      (node (ref "T8") (pin "2") (pinfunction "2_2") (pintype "passive"))
      (node (ref "T8") (pin "4") (pinfunction "4_4") (pintype "passive"))
      (node (ref "T8") (pin "5") (pinfunction "5_5") (pintype "passive"))
      (node (ref "T8") (pin "6") (pinfunction "6_6") (pintype "passive"))
      (node (ref "T8") (pin "7") (pinfunction "7_7") (pintype "passive"))
      (node (ref "T8") (pin "8") (pinfunction "8_8") (pintype "passive"))
      (node (ref "U1") (pin "1") (pinfunction "E/D_COM_1") (pintype "power_in"))
      (node (ref "U10") (pin "1") (pinfunction "E/D_COM_1") (pintype "power_in"))
      (node (ref "U11") (pin "1") (pinfunction "E/D_COM_1") (pintype "power_in"))
      (node (ref "U12") (pin "1") (pinfunction "E/D_COM_1") (pintype "power_in"))
      (node (ref "U13") (pin "1") (pinfunction "E/D_COM_1") (pintype "power_in"))
      (node (ref "U14") (pin "1") (pinfunction "E/D_COM_1") (pintype "power_in"))
      (node (ref "U15") (pin "1") (pinfunction "E/D_COM_1") (pintype "power_in"))
      (node (ref "U16") (pin "1") (pinfunction "E/D_COM_1") (pintype "power_in"))
      (node (ref "U17") (pin "1") (pinfunction "E/D_COM_1") (pintype "power_in"))
      (node (ref "U18") (pin "1") (pinfunction "E/D_COM_1") (pintype "power_in"))
      (node (ref "U19") (pin "1") (pinfunction "E/D_COM_1") (pintype "power_in"))
      (node (ref "U2") (pin "1") (pinfunction "E/D_COM_1") (pintype "power_in"))
      (node (ref "U20") (pin "1") (pinfunction "E/D_COM_1") (pintype "power_in"))
      (node (ref "U3") (pin "1") (pinfunction "E/D_COM_1") (pintype "power_in"))
      (node (ref "U4") (pin "1") (pinfunction "E/D_COM_1") (pintype "power_in"))
      (node (ref "U5") (pin "1") (pinfunction "E/D_COM_1") (pintype "power_in"))
      (node (ref "U6") (pin "1") (pinfunction "E/D_COM_1") (pintype "power_in"))
      (node (ref "U7") (pin "1") (pinfunction "E/D_COM_1") (pintype "power_in"))
      (node (ref "U8") (pin "1") (pinfunction "E/D_COM_1") (pintype "power_in"))
      (node (ref "U9") (pin "1") (pinfunction "E/D_COM_1") (pintype "power_in"))
    )
    (net (code "73") (name "Net-(D2+-A)") (class "Default")
      (node (ref "Cadj+") (pin "1") (pinfunction "1_1") (pintype "passive"))
      (node (ref "D2+") (pin "2") (pinfunction "A_2") (pintype "passive"))
      (node (ref "R1+") (pin "1") (pinfunction "1_1") (pintype "passive"))
      (node (ref "R2+") (pin "2") (pinfunction "2_2") (pintype "passive"))
      (node (ref "U+") (pin "1") (pinfunction "ADJ_1") (pintype "input"))
    )
    (net (code "74") (name "Net-(D2--K)") (class "Default")
      (node (ref "Cadj-") (pin "1") (pinfunction "1_1") (pintype "passive"))
      (node (ref "D2-") (pin "1") (pinfunction "K_1") (pintype "passive"))
      (node (ref "R1-") (pin "1") (pinfunction "1_1") (pintype "passive"))
      (node (ref "R2-") (pin "2") (pinfunction "2_2") (pintype "passive"))
      (node (ref "U-") (pin "1") (pinfunction "ADJ_1") (pintype "input"))
    )
    (net (code "75") (name "Net-(R2+-Pad1)") (class "Default")
      (node (ref "R2+") (pin "1") (pinfunction "1_1") (pintype "passive"))
      (node (ref "R3+") (pin "1") (pinfunction "1_1") (pintype "passive"))
    )
    (net (code "76") (name "Net-(R2--Pad1)") (class "Default")
      (node (ref "R2-") (pin "1") (pinfunction "1_1") (pintype "passive"))
      (node (ref "R3-") (pin "2") (pinfunction "2_2") (pintype "passive"))
    )
    (net (code "77") (name "Net-(T1-RF)") (class "Default")
      (node (ref "J1") (pin "1") (pinfunction "1_1") (pintype "passive"))
      (node (ref "T1") (pin "9") (pinfunction "RF_9") (pintype "input"))
    )
    (net (code "78") (name "Net-(T3-RF)") (class "Default")
      (node (ref "J3") (pin "1") (pinfunction "1_1") (pintype "passive"))
      (node (ref "T3") (pin "9") (pinfunction "RF_9") (pintype "input"))
    )
    (net (code "79") (name "Net-(T8-RF)") (class "Default")
      (node (ref "J8") (pin "1") (pinfunction "1_1") (pintype "passive"))
      (node (ref "T8") (pin "9") (pinfunction "RF_9") (pintype "input"))
    )
    (net (code "80") (name "Net-(T10-RF)") (class "Default")
      (node (ref "J10") (pin "1") (pinfunction "1_1") (pintype "passive"))
      (node (ref "T10") (pin "9") (pinfunction "RF_9") (pintype "input"))
    )
    (net (code "81") (name "Net-(T12-RF)") (class "Default")
      (node (ref "J12") (pin "1") (pinfunction "1_1") (pintype "passive"))
      (node (ref "T12") (pin "9") (pinfunction "RF_9") (pintype "input"))
    )
    (net (code "82") (name "Net-(T19-RF)") (class "Default")
      (node (ref "J19") (pin "1") (pinfunction "1_1") (pintype "passive"))
      (node (ref "T19") (pin "9") (pinfunction "RF_9") (pintype "input"))
    )
    (net (code "83") (name "Net-(U1-IN-)") (class "Default")
      (node (ref "Rf1") (pin "1") (pinfunction "1_1") (pintype "passive"))
      (node (ref "Rg1") (pin "2") (pinfunction "2_2") (pintype "passive"))
      (node (ref "U1") (pin "2") (pinfunction "IN-_2") (pintype "input"))
    )
    (net (code "84") (name "Net-(U1-STATUS_FLAG)") (class "Default")
      (node (ref "Re1") (pin "1") (pinfunction "1_1") (pintype "passive"))
      (node (ref "U1") (pin "5") (pinfunction "STATUS_FLAG_5") (pintype "open_collector"))
    )
    (net (code "85") (name "Net-(U2-IN-)") (class "Default")
      (node (ref "Rf2") (pin "1") (pinfunction "1_1") (pintype "passive"))
      (node (ref "Rg2") (pin "2") (pinfunction "2_2") (pintype "passive"))
      (node (ref "U2") (pin "2") (pinfunction "IN-_2") (pintype "input"))
    )
    (net (code "86") (name "Net-(U2-STATUS_FLAG)") (class "Default")
      (node (ref "Re2") (pin "1") (pinfunction "1_1") (pintype "passive"))
      (node (ref "U2") (pin "5") (pinfunction "STATUS_FLAG_5") (pintype "open_collector"))
    )
    (net (code "87") (name "Net-(U3-IN-)") (class "Default")
      (node (ref "Rf3") (pin "1") (pinfunction "1_1") (pintype "passive"))
      (node (ref "Rg3") (pin "2") (pinfunction "2_2") (pintype "passive"))
      (node (ref "U3") (pin "2") (pinfunction "IN-_2") (pintype "input"))
    )
    (net (code "88") (name "Net-(U3-STATUS_FLAG)") (class "Default")
      (node (ref "Re3") (pin "1") (pinfunction "1_1") (pintype "passive"))
      (node (ref "U3") (pin "5") (pinfunction "STATUS_FLAG_5") (pintype "open_collector"))
    )
    (net (code "89") (name "Net-(U4-IN-)") (class "Default")
      (node (ref "Rf4") (pin "1") (pinfunction "1_1") (pintype "passive"))
      (node (ref "Rg4") (pin "2") (pinfunction "2_2") (pintype "passive"))
      (node (ref "U4") (pin "2") (pinfunction "IN-_2") (pintype "input"))
    )
    (net (code "90") (name "Net-(U4-STATUS_FLAG)") (class "Default")
      (node (ref "Re4") (pin "1") (pinfunction "1_1") (pintype "passive"))
      (node (ref "U4") (pin "5") (pinfunction "STATUS_FLAG_5") (pintype "open_collector"))
    )
    (net (code "91") (name "Net-(U5-IN-)") (class "Default")
      (node (ref "Rf5") (pin "1") (pinfunction "1_1") (pintype "passive"))
      (node (ref "Rg5") (pin "2") (pinfunction "2_2") (pintype "passive"))
      (node (ref "U5") (pin "2") (pinfunction "IN-_2") (pintype "input"))
    )
    (net (code "92") (name "Net-(U5-STATUS_FLAG)") (class "Default")
      (node (ref "Re5") (pin "1") (pinfunction "1_1") (pintype "passive"))
      (node (ref "U5") (pin "5") (pinfunction "STATUS_FLAG_5") (pintype "open_collector"))
    )
    (net (code "93") (name "Net-(U6-IN-)") (class "Default")
      (node (ref "Rf6") (pin "1") (pinfunction "1_1") (pintype "passive"))
      (node (ref "Rg6") (pin "2") (pinfunction "2_2") (pintype "passive"))
      (node (ref "U6") (pin "2") (pinfunction "IN-_2") (pintype "input"))
    )
    (net (code "94") (name "Net-(U6-STATUS_FLAG)") (class "Default")
      (node (ref "Re6") (pin "1") (pinfunction "1_1") (pintype "passive"))
      (node (ref "U6") (pin "5") (pinfunction "STATUS_FLAG_5") (pintype "open_collector"))
    )
    (net (code "95") (name "Net-(U7-IN-)") (class "Default")
      (node (ref "Rf7") (pin "1") (pinfunction "1_1") (pintype "passive"))
      (node (ref "Rg7") (pin "2") (pinfunction "2_2") (pintype "passive"))
      (node (ref "U7") (pin "2") (pinfunction "IN-_2") (pintype "input"))
    )
    (net (code "96") (name "Net-(U7-STATUS_FLAG)") (class "Default")
      (node (ref "Re7") (pin "1") (pinfunction "1_1") (pintype "passive"))
      (node (ref "U7") (pin "5") (pinfunction "STATUS_FLAG_5") (pintype "open_collector"))
    )
    (net (code "97") (name "Net-(U8-IN-)") (class "Default")
      (node (ref "Rf8") (pin "1") (pinfunction "1_1") (pintype "passive"))
      (node (ref "Rg8") (pin "2") (pinfunction "2_2") (pintype "passive"))
      (node (ref "U8") (pin "2") (pinfunction "IN-_2") (pintype "input"))
    )
    (net (code "98") (name "Net-(U8-STATUS_FLAG)") (class "Default")
      (node (ref "Re8") (pin "1") (pinfunction "1_1") (pintype "passive"))
      (node (ref "U8") (pin "5") (pinfunction "STATUS_FLAG_5") (pintype "open_collector"))
    )
    (net (code "99") (name "Net-(U9-IN-)") (class "Default")
      (node (ref "Rf9") (pin "1") (pinfunction "1_1") (pintype "passive"))
      (node (ref "Rg9") (pin "2") (pinfunction "2_2") (pintype "passive"))
      (node (ref "U9") (pin "2") (pinfunction "IN-_2") (pintype "input"))
    )
    (net (code "100") (name "Net-(U9-STATUS_FLAG)") (class "Default")
      (node (ref "Re9") (pin "1") (pinfunction "1_1") (pintype "passive"))
      (node (ref "U9") (pin "5") (pinfunction "STATUS_FLAG_5") (pintype "open_collector"))
    )
    (net (code "101") (name "Net-(U10-IN-)") (class "Default")
      (node (ref "Rf10") (pin "1") (pinfunction "1_1") (pintype "passive"))
      (node (ref "Rg10") (pin "2") (pinfunction "2_2") (pintype "passive"))
      (node (ref "U10") (pin "2") (pinfunction "IN-_2") (pintype "input"))
    )
    (net (code "102") (name "Net-(U10-STATUS_FLAG)") (class "Default")
      (node (ref "Re10") (pin "1") (pinfunction "1_1") (pintype "passive"))
      (node (ref "U10") (pin "5") (pinfunction "STATUS_FLAG_5") (pintype "open_collector"))
    )
    (net (code "103") (name "Net-(U11-IN-)") (class "Default")
      (node (ref "Rf11") (pin "1") (pinfunction "1_1") (pintype "passive"))
      (node (ref "Rg11") (pin "2") (pinfunction "2_2") (pintype "passive"))
      (node (ref "U11") (pin "2") (pinfunction "IN-_2") (pintype "input"))
    )
    (net (code "104") (name "Net-(U11-STATUS_FLAG)") (class "Default")
      (node (ref "Re11") (pin "1") (pinfunction "1_1") (pintype "passive"))
      (node (ref "U11") (pin "5") (pinfunction "STATUS_FLAG_5") (pintype "open_collector"))
    )
    (net (code "105") (name "Net-(U12-IN-)") (class "Default")
      (node (ref "Rf12") (pin "1") (pinfunction "1_1") (pintype "passive"))
      (node (ref "Rg12") (pin "2") (pinfunction "2_2") (pintype "passive"))
      (node (ref "U12") (pin "2") (pinfunction "IN-_2") (pintype "input"))
    )
    (net (code "106") (name "Net-(U12-STATUS_FLAG)") (class "Default")
      (node (ref "Re12") (pin "1") (pinfunction "1_1") (pintype "passive"))
      (node (ref "U12") (pin "5") (pinfunction "STATUS_FLAG_5") (pintype "open_collector"))
    )
    (net (code "107") (name "Net-(U13-IN-)") (class "Default")
      (node (ref "Rf13") (pin "1") (pinfunction "1_1") (pintype "passive"))
      (node (ref "Rg13") (pin "2") (pinfunction "2_2") (pintype "passive"))
      (node (ref "U13") (pin "2") (pinfunction "IN-_2") (pintype "input"))
    )
    (net (code "108") (name "Net-(U13-STATUS_FLAG)") (class "Default")
      (node (ref "Re13") (pin "1") (pinfunction "1_1") (pintype "passive"))
      (node (ref "U13") (pin "5") (pinfunction "STATUS_FLAG_5") (pintype "open_collector"))
    )
    (net (code "109") (name "Net-(U14-IN-)") (class "Default")
      (node (ref "Rf14") (pin "1") (pinfunction "1_1") (pintype "passive"))
      (node (ref "Rg14") (pin "2") (pinfunction "2_2") (pintype "passive"))
      (node (ref "U14") (pin "2") (pinfunction "IN-_2") (pintype "input"))
    )
    (net (code "110") (name "Net-(U14-STATUS_FLAG)") (class "Default")
      (node (ref "Re14") (pin "1") (pinfunction "1_1") (pintype "passive"))
      (node (ref "U14") (pin "5") (pinfunction "STATUS_FLAG_5") (pintype "open_collector"))
    )
    (net (code "111") (name "Net-(U15-IN-)") (class "Default")
      (node (ref "Rf15") (pin "1") (pinfunction "1_1") (pintype "passive"))
      (node (ref "Rg15") (pin "2") (pinfunction "2_2") (pintype "passive"))
      (node (ref "U15") (pin "2") (pinfunction "IN-_2") (pintype "input"))
    )
    (net (code "112") (name "Net-(U15-STATUS_FLAG)") (class "Default")
      (node (ref "Re15") (pin "1") (pinfunction "1_1") (pintype "passive"))
      (node (ref "U15") (pin "5") (pinfunction "STATUS_FLAG_5") (pintype "open_collector"))
    )
    (net (code "113") (name "Net-(U16-IN-)") (class "Default")
      (node (ref "Rf16") (pin "1") (pinfunction "1_1") (pintype "passive"))
      (node (ref "Rg16") (pin "2") (pinfunction "2_2") (pintype "passive"))
      (node (ref "U16") (pin "2") (pinfunction "IN-_2") (pintype "input"))
    )
    (net (code "114") (name "Net-(U16-STATUS_FLAG)") (class "Default")
      (node (ref "Re16") (pin "1") (pinfunction "1_1") (pintype "passive"))
      (node (ref "U16") (pin "5") (pinfunction "STATUS_FLAG_5") (pintype "open_collector"))
    )
    (net (code "115") (name "Net-(U17-IN-)") (class "Default")
      (node (ref "Rf17") (pin "1") (pinfunction "1_1") (pintype "passive"))
      (node (ref "Rg17") (pin "2") (pinfunction "2_2") (pintype "passive"))
      (node (ref "U17") (pin "2") (pinfunction "IN-_2") (pintype "input"))
    )
    (net (code "116") (name "Net-(U17-STATUS_FLAG)") (class "Default")
      (node (ref "Re17") (pin "1") (pinfunction "1_1") (pintype "passive"))
      (node (ref "U17") (pin "5") (pinfunction "STATUS_FLAG_5") (pintype "open_collector"))
    )
    (net (code "117") (name "Net-(U18-IN-)") (class "Default")
      (node (ref "Rf18") (pin "1") (pinfunction "1_1") (pintype "passive"))
      (node (ref "Rg18") (pin "2") (pinfunction "2_2") (pintype "passive"))
      (node (ref "U18") (pin "2") (pinfunction "IN-_2") (pintype "input"))
    )
    (net (code "118") (name "Net-(U18-STATUS_FLAG)") (class "Default")
      (node (ref "Re18") (pin "1") (pinfunction "1_1") (pintype "passive"))
      (node (ref "U18") (pin "5") (pinfunction "STATUS_FLAG_5") (pintype "open_collector"))
    )
    (net (code "119") (name "Net-(U19-IN-)") (class "Default")
      (node (ref "Rf19") (pin "1") (pinfunction "1_1") (pintype "passive"))
      (node (ref "Rg19") (pin "2") (pinfunction "2_2") (pintype "passive"))
      (node (ref "U19") (pin "2") (pinfunction "IN-_2") (pintype "input"))
    )
    (net (code "120") (name "Net-(U19-STATUS_FLAG)") (class "Default")
      (node (ref "Re19") (pin "1") (pinfunction "1_1") (pintype "passive"))
      (node (ref "U19") (pin "5") (pinfunction "STATUS_FLAG_5") (pintype "open_collector"))
    )
    (net (code "121") (name "Net-(U20-IN-)") (class "Default")
      (node (ref "Rf20") (pin "1") (pinfunction "1_1") (pintype "passive"))
      (node (ref "Rg20") (pin "2") (pinfunction "2_2") (pintype "passive"))
      (node (ref "U20") (pin "2") (pinfunction "IN-_2") (pintype "input"))
    )
    (net (code "122") (name "Net-(U20-STATUS_FLAG)") (class "Default")
      (node (ref "Re20") (pin "1") (pinfunction "1_1") (pintype "passive"))
      (node (ref "U20") (pin "5") (pinfunction "STATUS_FLAG_5") (pintype "open_collector"))
    )
    (net (code "123") (name "unconnected-(JIN-Z20-Pad23)") (class "Default")
      (node (ref "JIN") (pin "23") (pinfunction "Z20_23") (pintype "passive"))
    )
    (net (code "124") (name "unconnected-(JIN-Z21-Pad24)") (class "Default")
      (node (ref "JIN") (pin "24") (pinfunction "Z21_24") (pintype "passive"))
    )
    (net (code "125") (name "unconnected-(JIN-Z22-Pad25)") (class "Default")
      (node (ref "JIN") (pin "25") (pinfunction "Z22_25") (pintype "passive"))
    )
    (net (code "126") (name "unconnected-(JIN-Z23-Pad26)") (class "Default")
      (node (ref "JIN") (pin "26") (pinfunction "Z23_26") (pintype "passive"))
    )
    (net (code "127") (name "unconnected-(JIN-Z24-Pad27)") (class "Default")
      (node (ref "JIN") (pin "27") (pinfunction "Z24_27") (pintype "passive"))
    )
    (net (code "128") (name "unconnected-(JIN-Z25-Pad28)") (class "Default")
      (node (ref "JIN") (pin "28") (pinfunction "Z25_28") (pintype "passive"))
    )
    (net (code "129") (name "unconnected-(JIN-Z26-Pad29)") (class "Default")
      (node (ref "JIN") (pin "29") (pinfunction "Z26_29") (pintype "passive"))
    )
    (net (code "130") (name "unconnected-(JIN-Z27-Pad30)") (class "Default")
      (node (ref "JIN") (pin "30") (pinfunction "Z27_30") (pintype "passive"))
    )
    (net (code "131") (name "unconnected-(JIN-Z28-Pad31)") (class "Default")
      (node (ref "JIN") (pin "31") (pinfunction "Z28_31") (pintype "passive"))
    )
    (net (code "132") (name "unconnected-(JIN-Z29-Pad32)") (class "Default")
      (node (ref "JIN") (pin "32") (pinfunction "Z29_32") (pintype "passive"))
    )
    (net (code "133") (name "unconnected-(JIN-Z30-Pad33)") (class "Default")
      (node (ref "JIN") (pin "33") (pinfunction "Z30_33") (pintype "passive"))
    )
    (net (code "134") (name "unconnected-(JIN-Z31-Pad34)") (class "Default")
      (node (ref "JIN") (pin "34") (pinfunction "Z31_34") (pintype "passive"))
    )
  )
)
